# logicboard.net
KiCad netlist of a schematic drawn in EAGLE
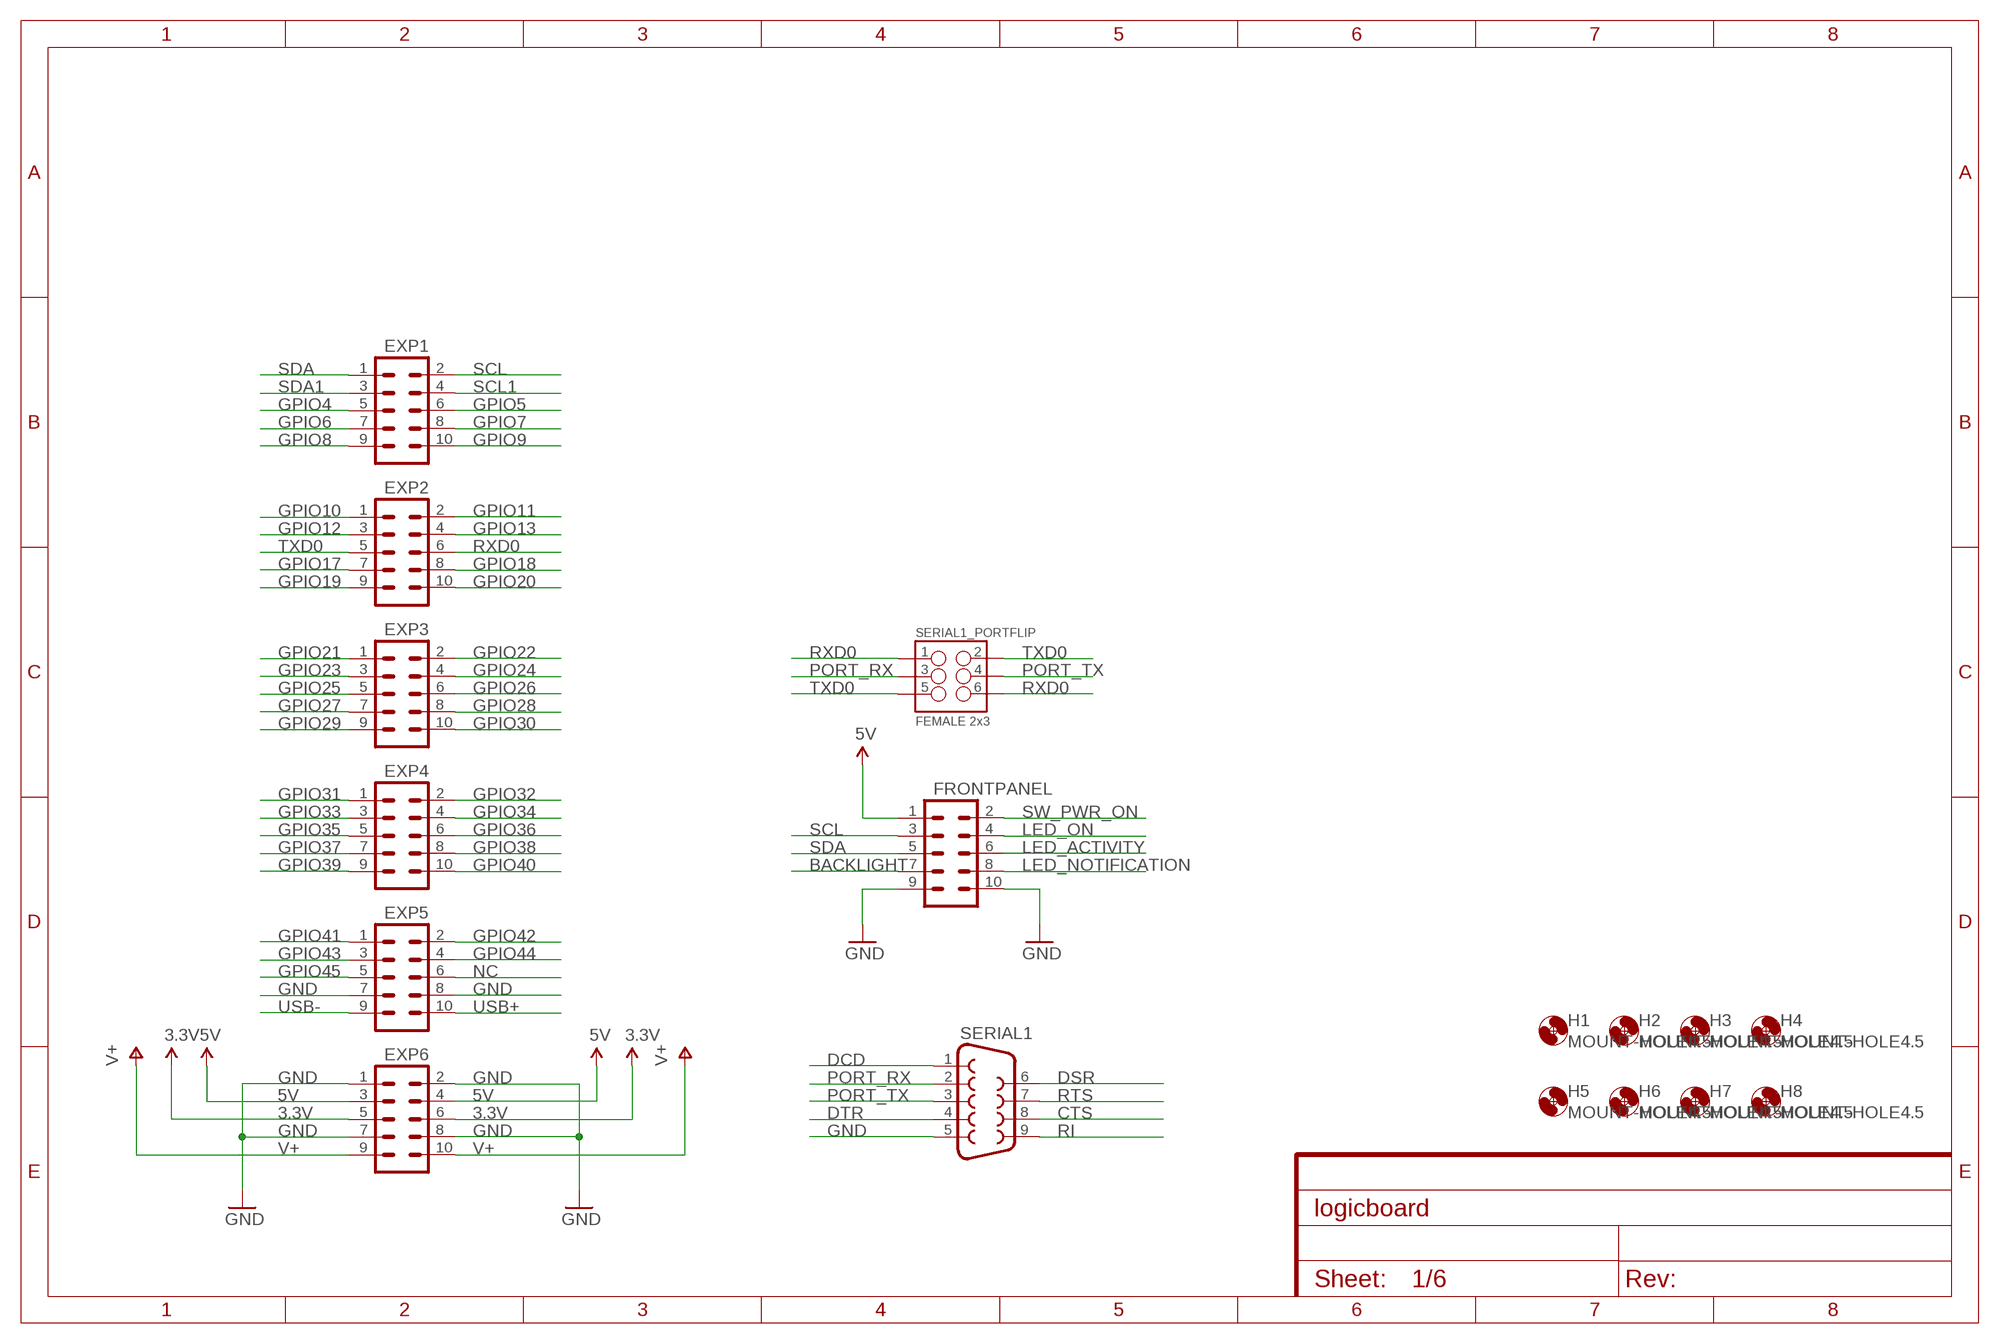
[diagram p0: schematic, sheet 1]
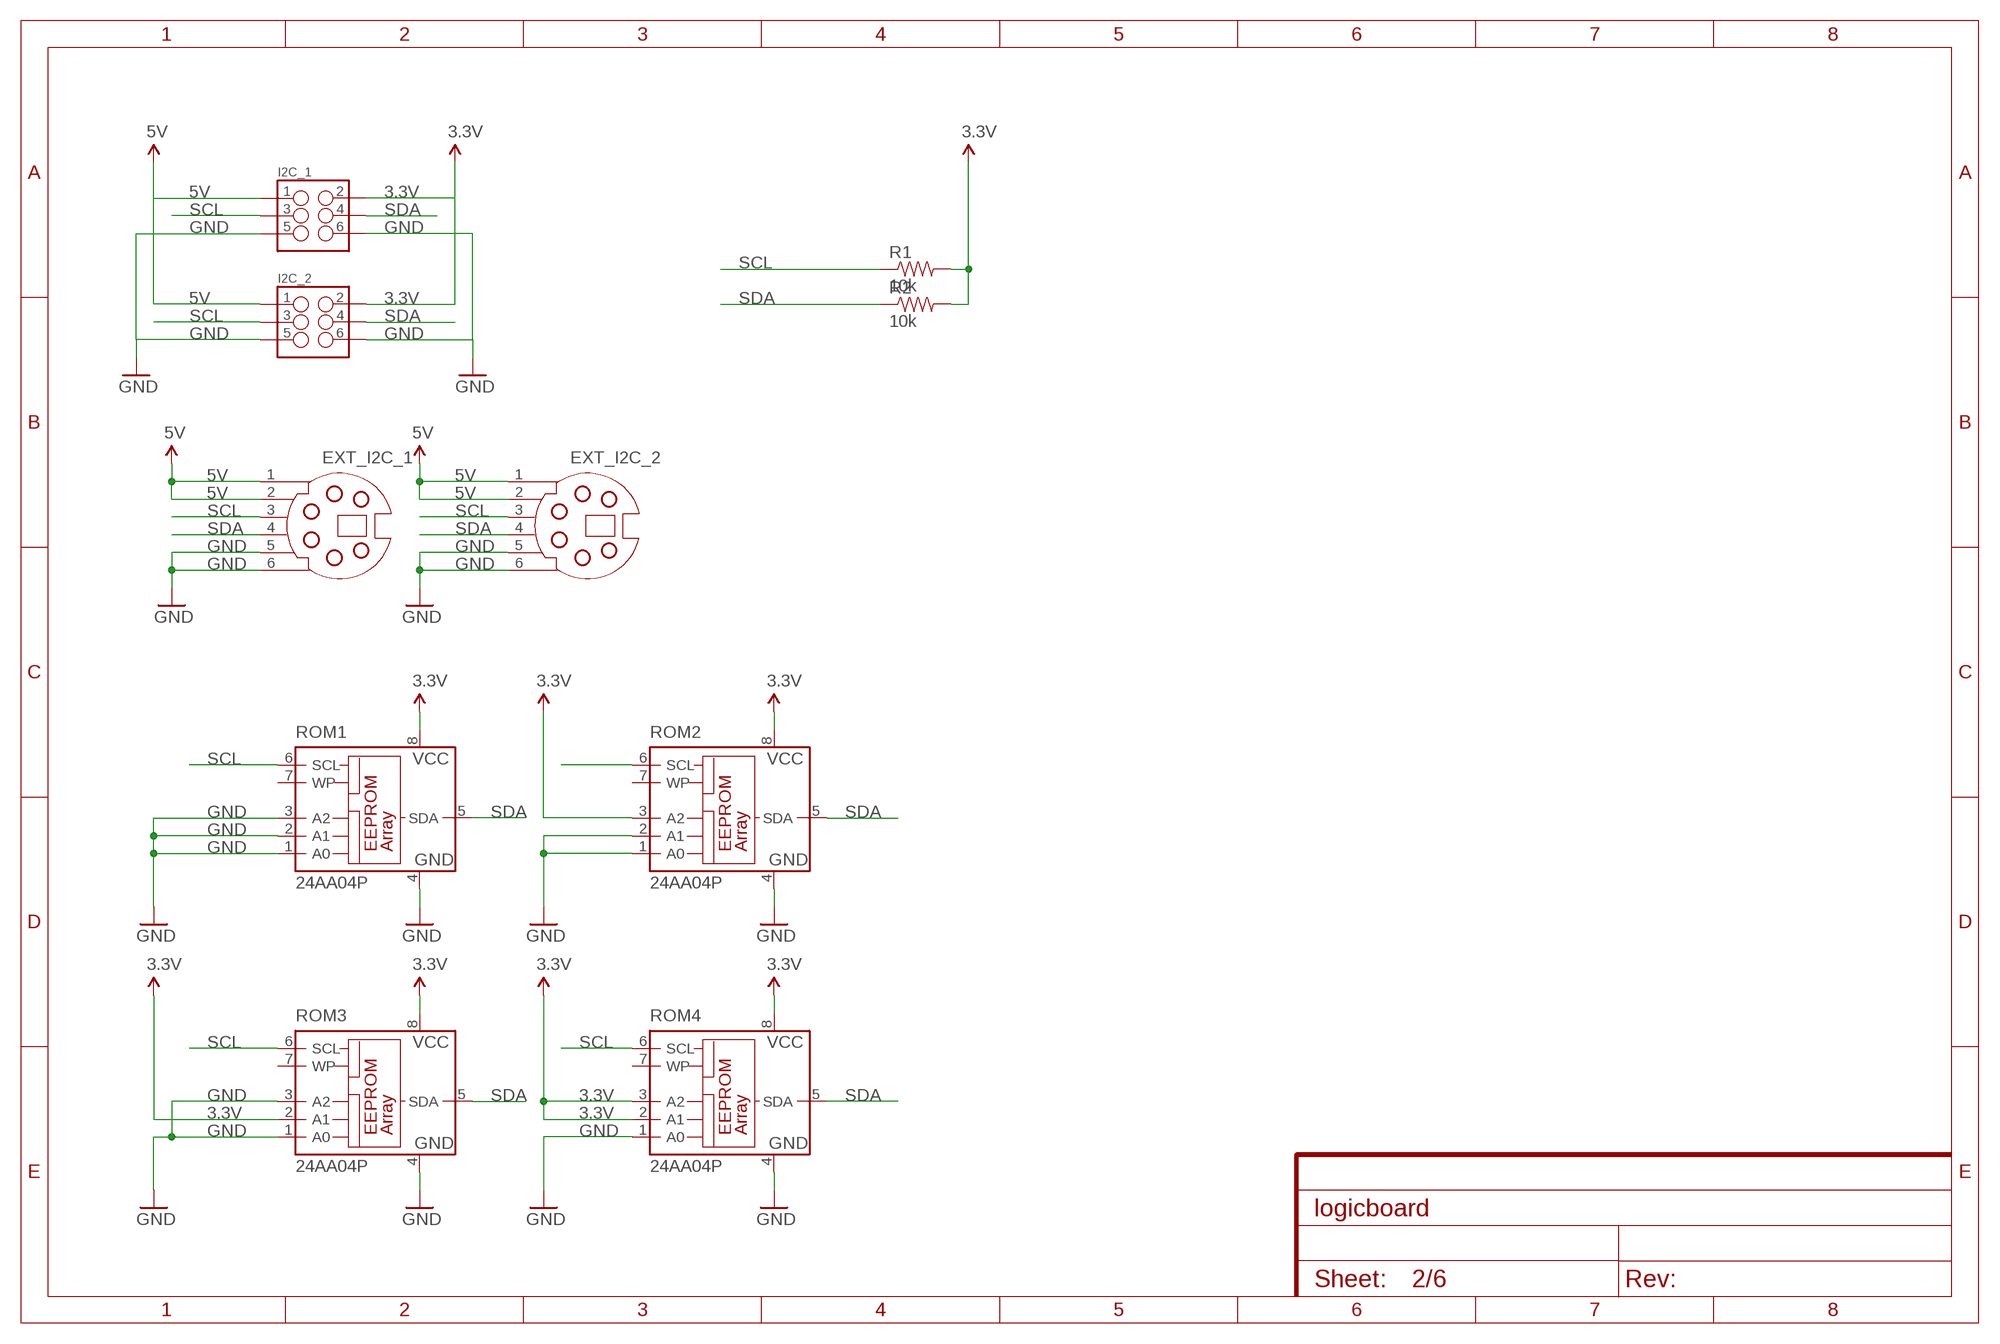
[diagram p1: schematic, sheet 2]
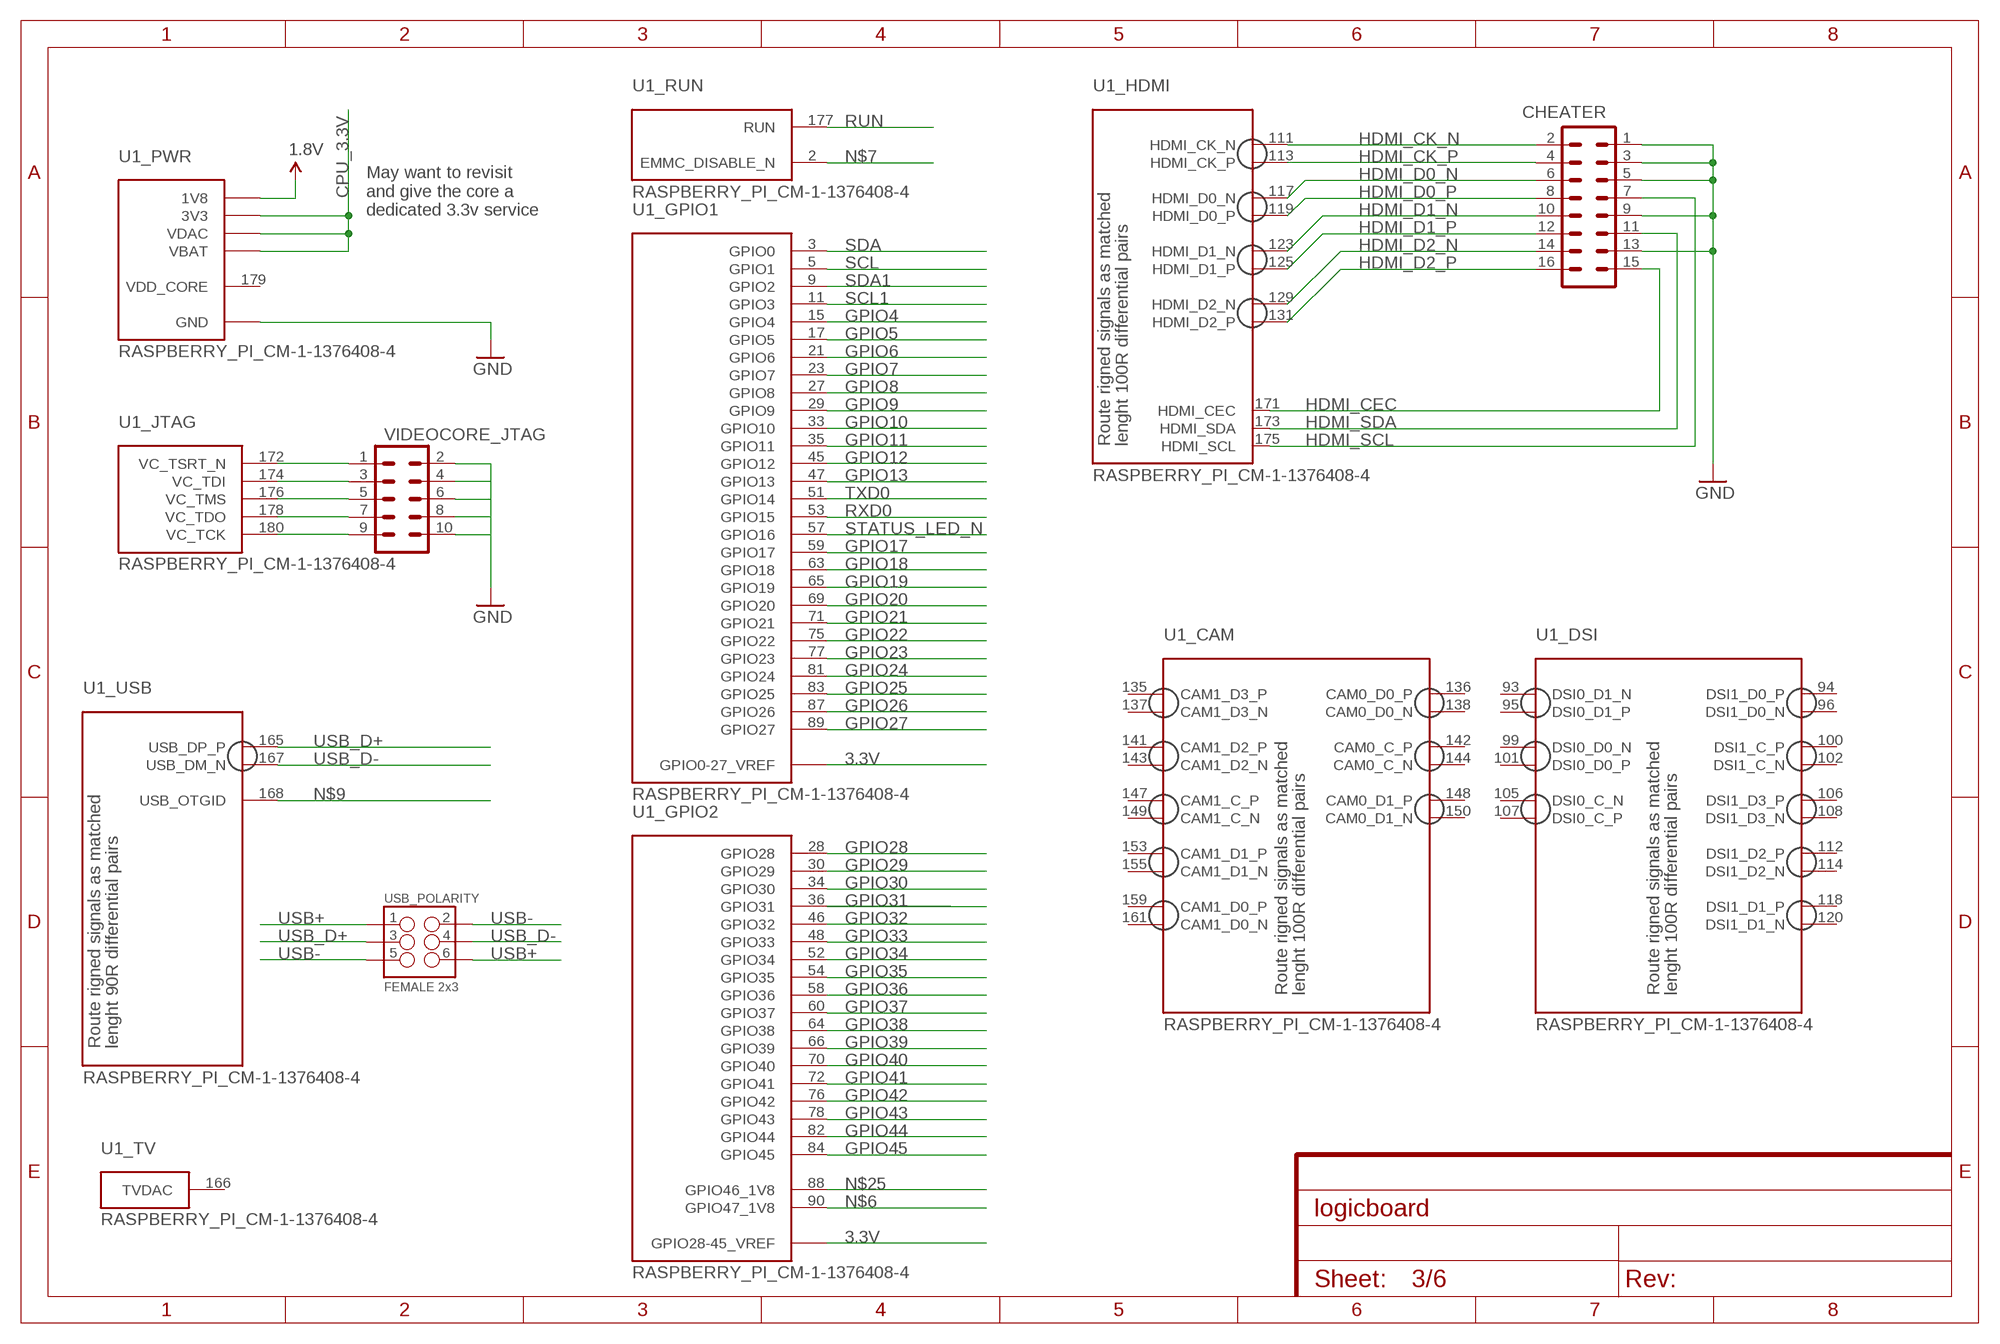
[diagram p2: schematic, sheet 3]
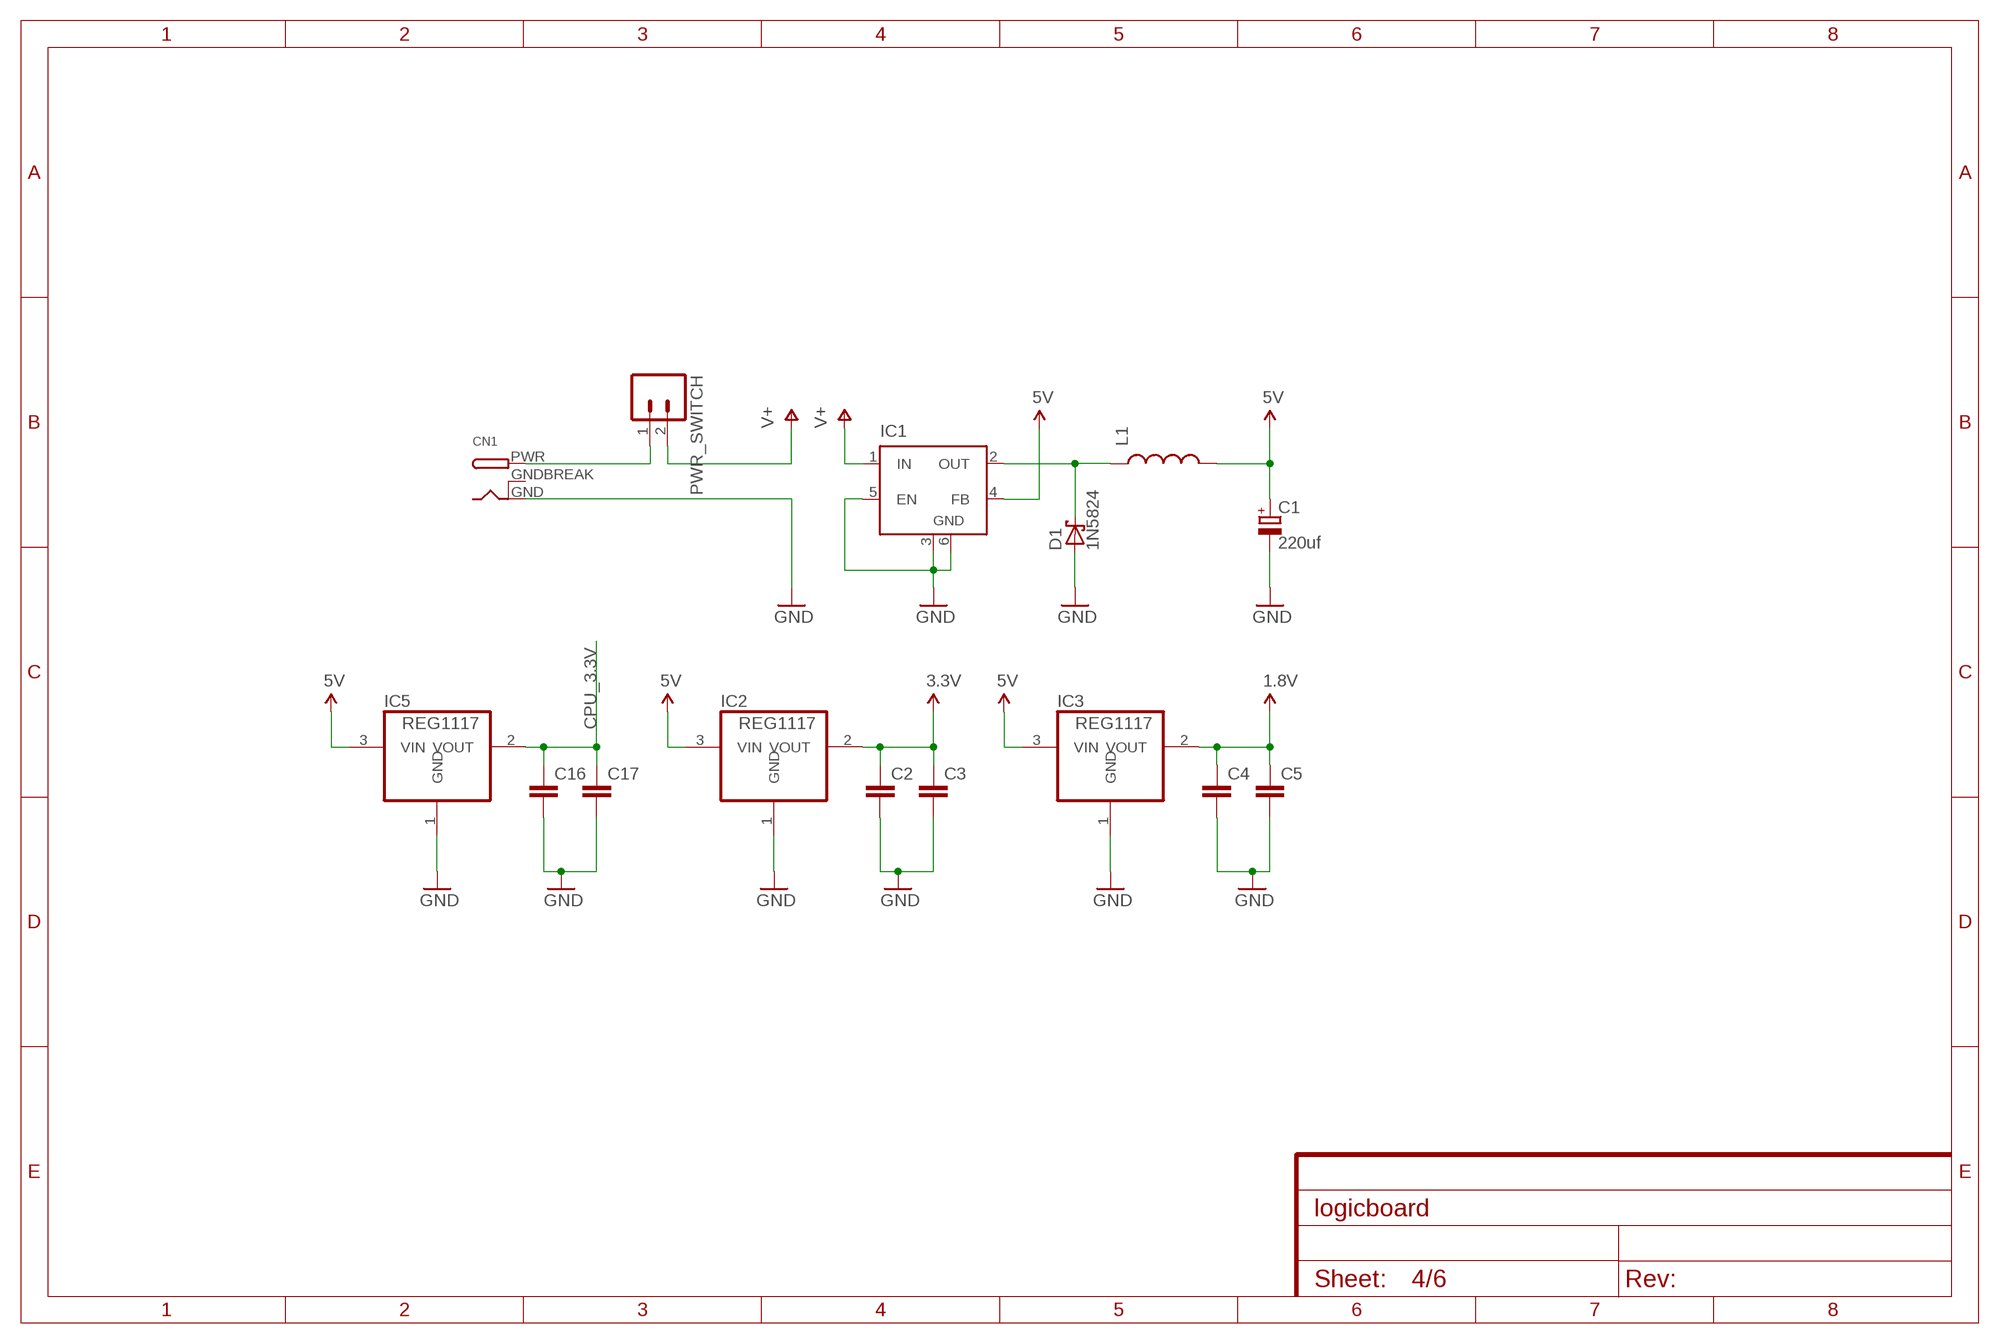
[diagram p3: schematic, sheet 4]
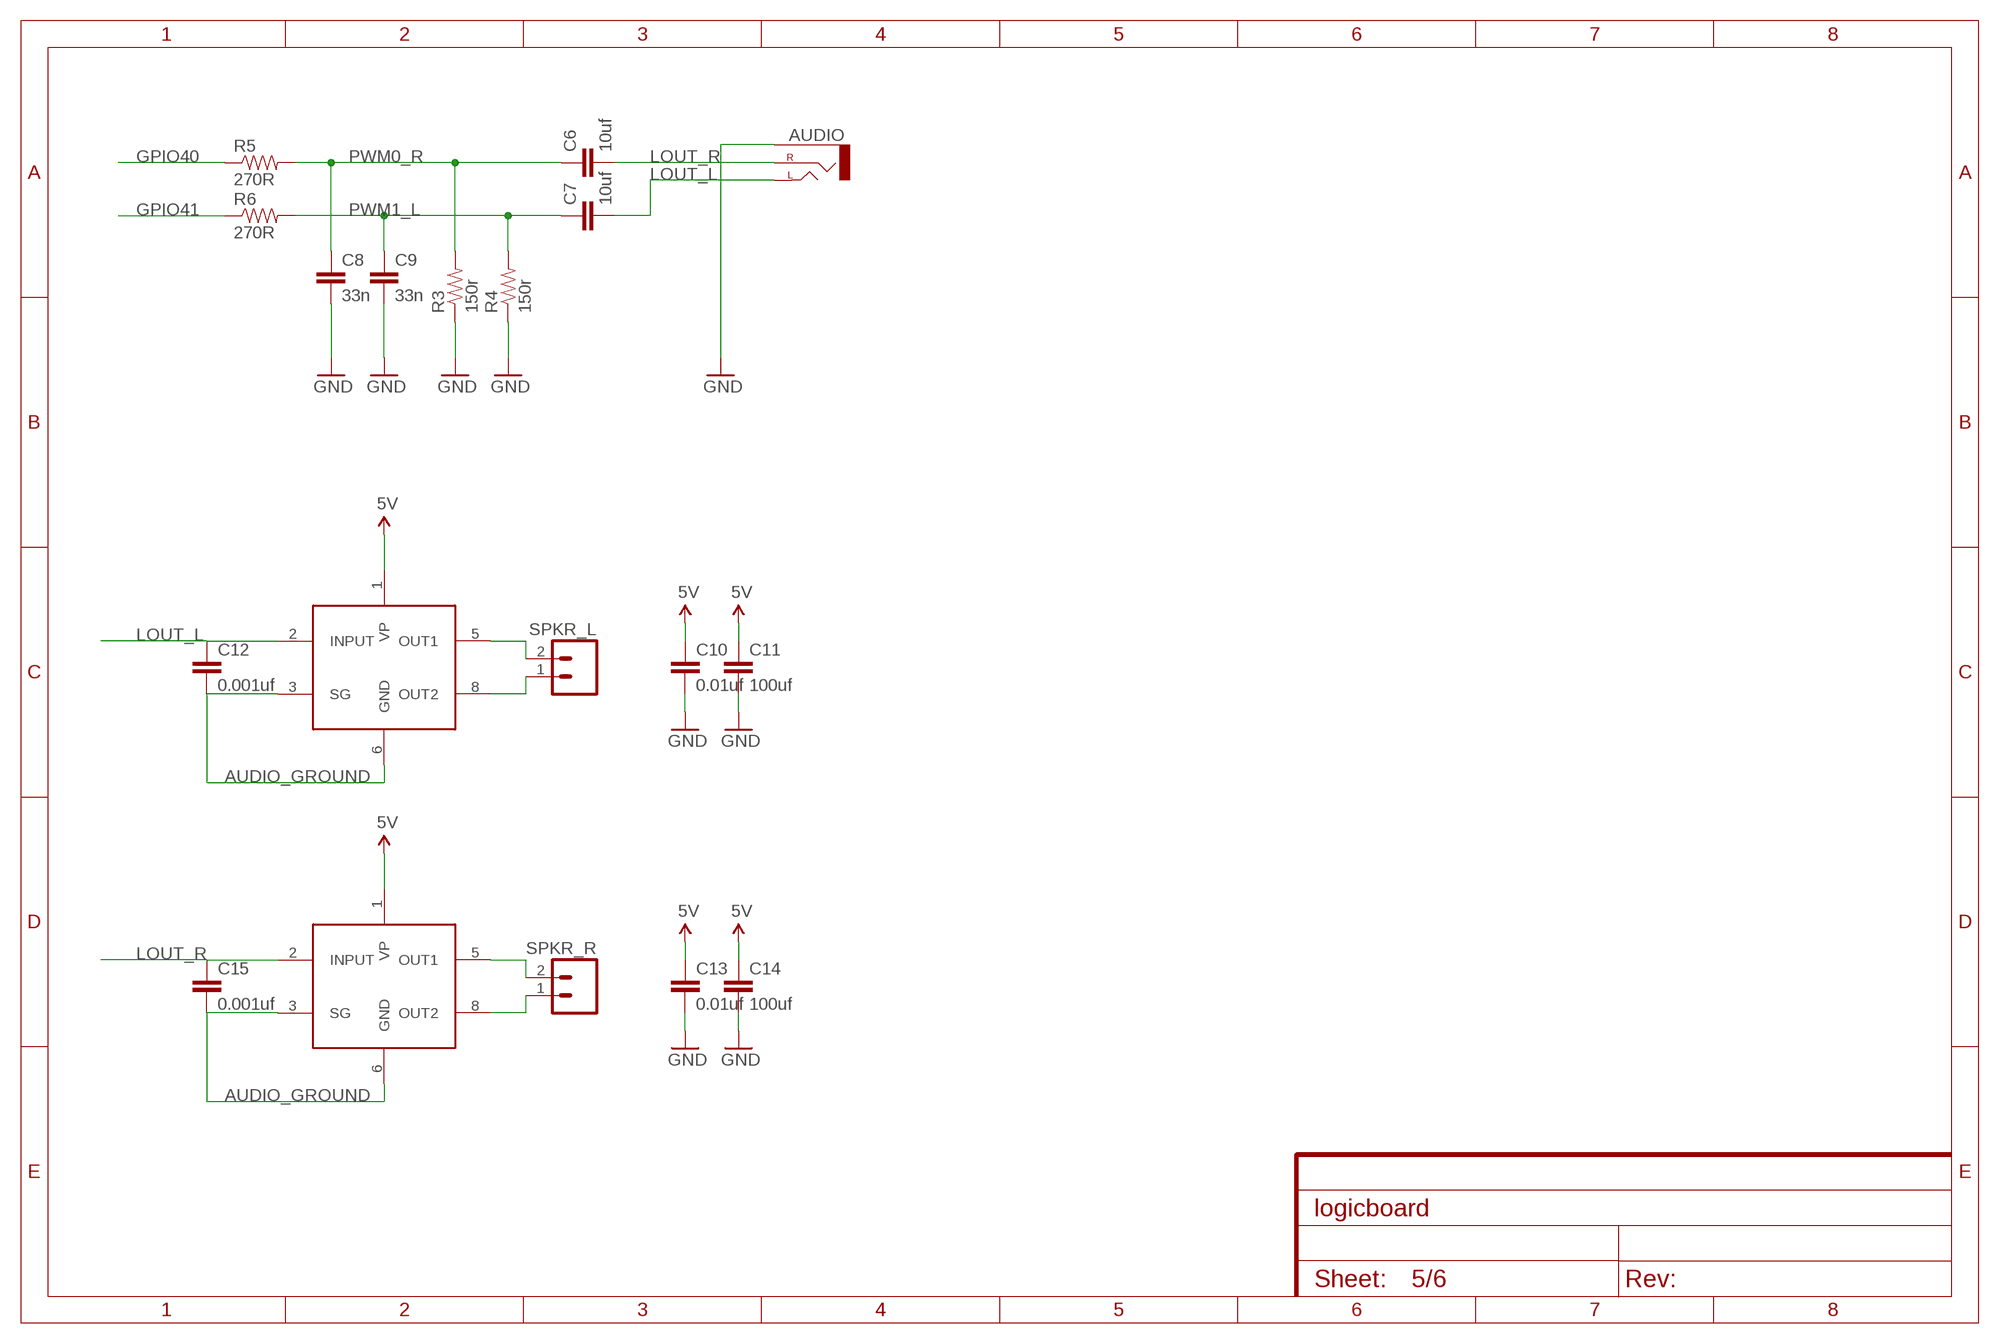
[diagram p4: schematic, sheet 5]
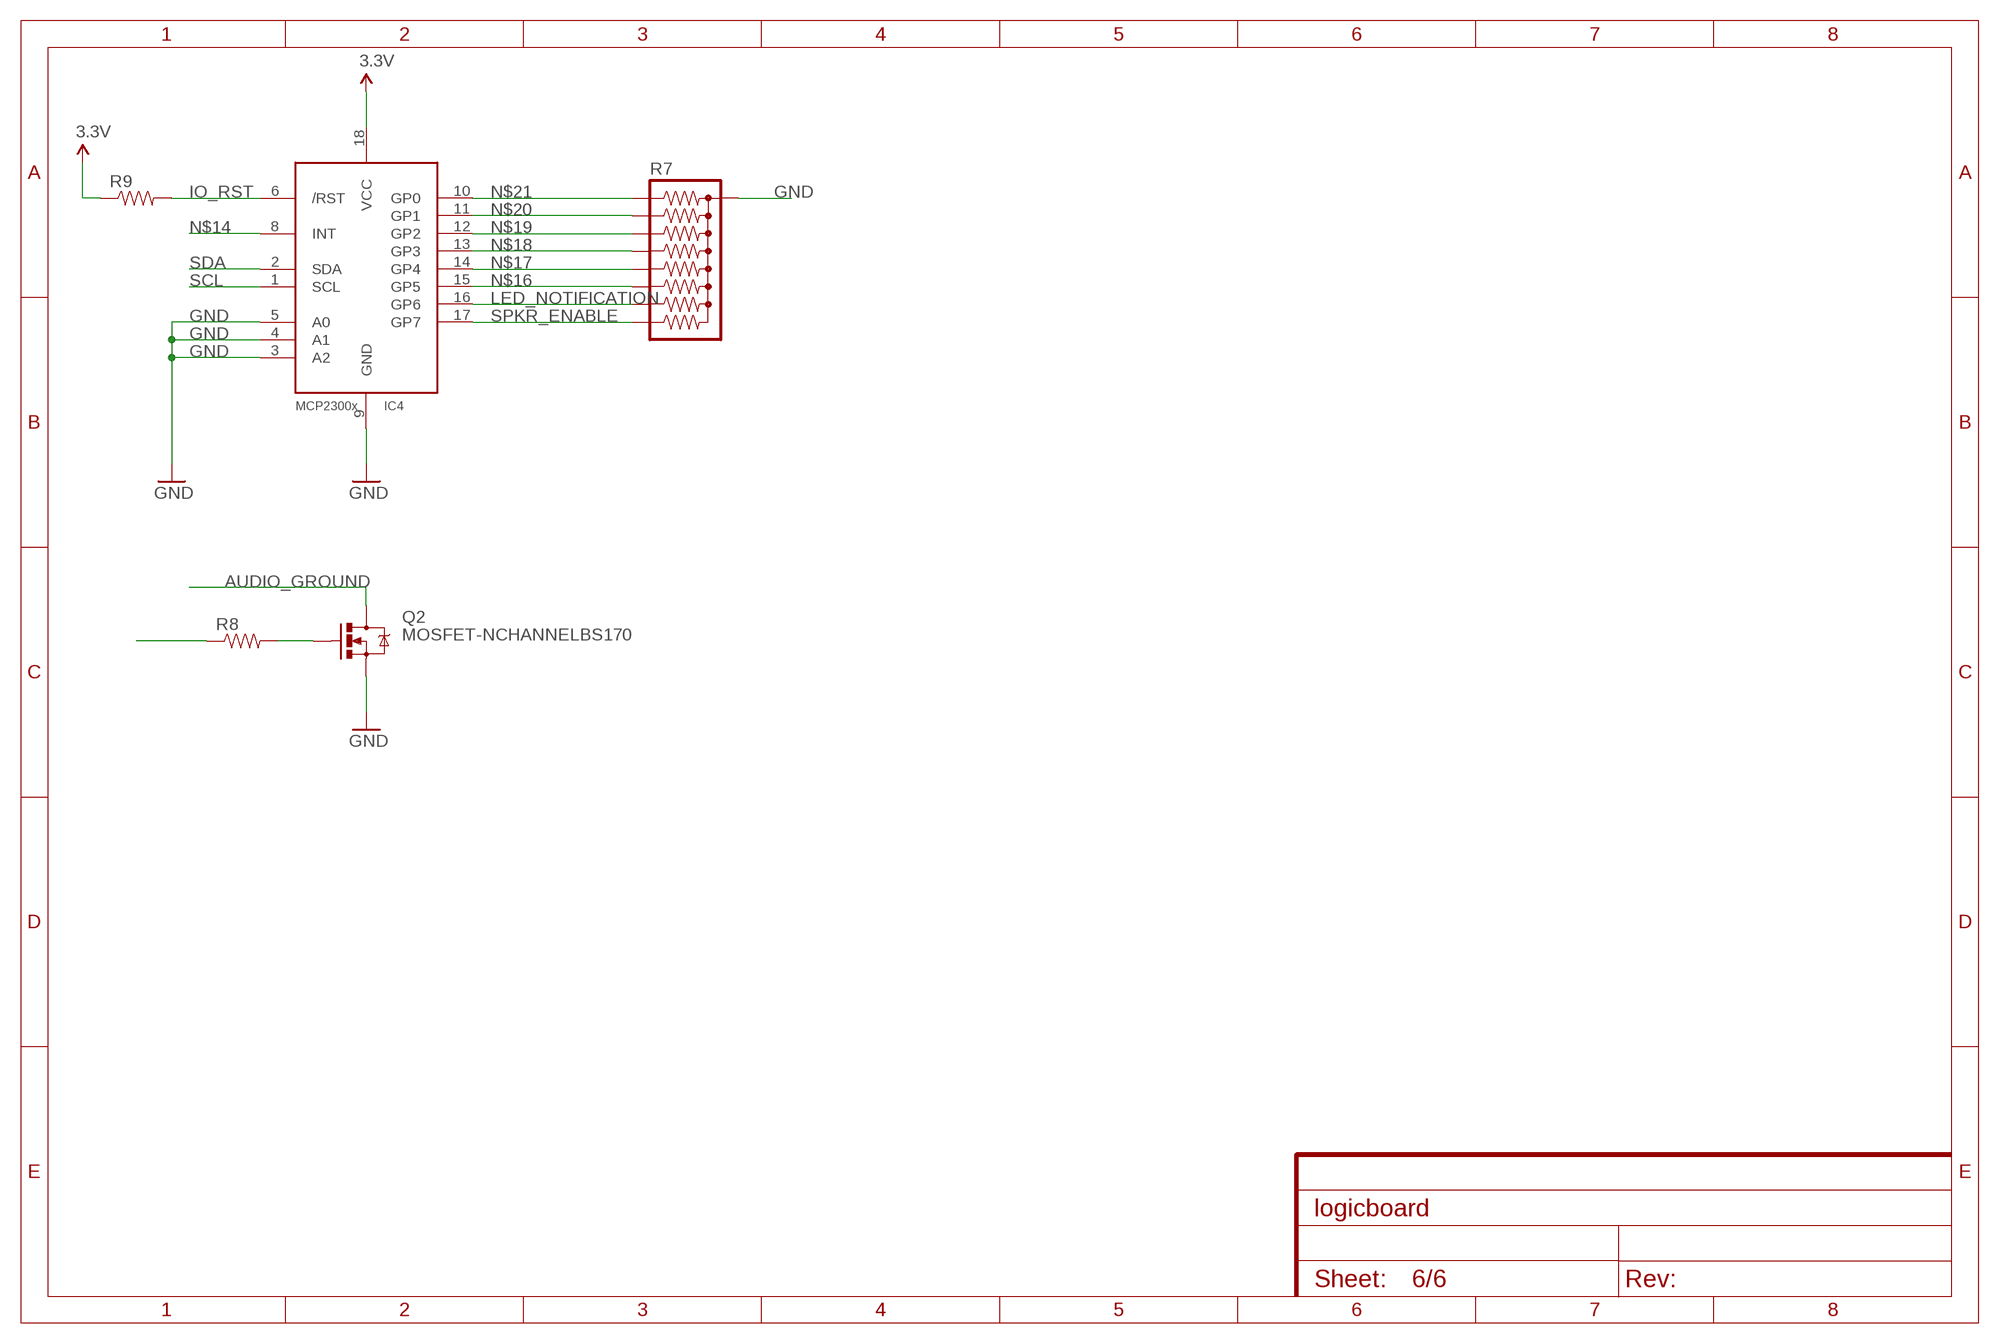
[diagram p5: schematic, sheet 6]

(export (version "E")
  (design (tool "Eeschema 10.0.6"))
  (components
    (comp (ref "AUDIO")
      (value "AUDIO-JACKPTH")
      (footprint "eagle-import:AUDIO-JACK")
      (libsource (lib "eagle-import") (part "AUDIO-JACKPTH"))
    )
    (comp (ref "C6")
      (value "10uf")
      (footprint "eagle-import:CAP-PTH-SMALLEZ")
      (libsource (lib "eagle-import") (part "CAPEZ"))
    )
    (comp (ref "C7")
      (value "10uf")
      (footprint "eagle-import:CAP-PTH-SMALLEZ")
      (libsource (lib "eagle-import") (part "CAPEZ"))
    )
    (comp (ref "C8")
      (value "33n")
      (footprint "eagle-import:CAP-PTH-SMALLEZ")
      (libsource (lib "eagle-import") (part "CAPEZ"))
    )
    (comp (ref "C9")
      (value "33n")
      (footprint "eagle-import:CAP-PTH-SMALLEZ")
      (libsource (lib "eagle-import") (part "CAPEZ"))
    )
    (comp (ref "C10")
      (value "0.01uf")
      (footprint "eagle-import:CAP-PTH-SMALLEZ")
      (libsource (lib "eagle-import") (part "CAPEZ"))
    )
    (comp (ref "C11")
      (value "100uf")
      (footprint "eagle-import:CAP-PTH-SMALLEZ")
      (libsource (lib "eagle-import") (part "CAPEZ"))
    )
    (comp (ref "C12")
      (value "0.001uf")
      (footprint "eagle-import:CAP-PTH-SMALLEZ")
      (libsource (lib "eagle-import") (part "CAPEZ"))
    )
    (comp (ref "C13")
      (value "0.01uf")
      (footprint "eagle-import:CAP-PTH-SMALLEZ")
      (libsource (lib "eagle-import") (part "CAPEZ"))
    )
    (comp (ref "C14")
      (value "100uf")
      (footprint "eagle-import:CAP-PTH-SMALLEZ")
      (libsource (lib "eagle-import") (part "CAPEZ"))
    )
    (comp (ref "C15")
      (value "0.001uf")
      (footprint "eagle-import:CAP-PTH-SMALLEZ")
      (libsource (lib "eagle-import") (part "CAPEZ"))
    )
    (comp (ref "R3")
      (value "150r")
      (footprint "eagle-import:AXIAL-0.3EZ")
      (libsource (lib "eagle-import") (part "RESISTOREZ"))
    )
    (comp (ref "R4")
      (value "150r")
      (footprint "eagle-import:AXIAL-0.3EZ")
      (libsource (lib "eagle-import") (part "RESISTOREZ"))
    )
    (comp (ref "R5")
      (value "270R")
      (footprint "eagle-import:AXIAL-0.3EZ")
      (libsource (lib "eagle-import") (part "RESISTOREZ"))
    )
    (comp (ref "R6")
      (value "270R")
      (footprint "eagle-import:AXIAL-0.3EZ")
      (libsource (lib "eagle-import") (part "RESISTOREZ"))
    )
    (comp (ref "SPKR_L")
      (value "M02JST-PTH-2-KIT")
      (footprint "eagle-import:JST-2-PTH-KIT")
      (libsource (lib "eagle-import") (part "M02JST-PTH-2-KIT"))
    )
    (comp (ref "SPKR_R")
      (value "M02JST-PTH-2-KIT")
      (footprint "eagle-import:JST-2-PTH-KIT")
      (libsource (lib "eagle-import") (part "M02JST-PTH-2-KIT"))
    )
    (comp (ref "U$1")
      (value "TDA7052")
      (footprint "eagle-import:DIL08")
      (libsource (lib "eagle-import") (part "TDA7052"))
    )
    (comp (ref "U$2")
      (value "TDA7052")
      (footprint "eagle-import:DIL08")
      (libsource (lib "eagle-import") (part "TDA7052"))
    )
    (comp (ref "EXP1")
      (value "M05X2SHD_LOCK")
      (footprint "eagle-import:2X5-SHROUDED_LOCK")
      (libsource (lib "eagle-import") (part "M05X2SHD_LOCK"))
    )
    (comp (ref "EXP2")
      (value "M05X2SHD_LOCK")
      (footprint "eagle-import:2X5-SHROUDED_LOCK")
      (libsource (lib "eagle-import") (part "M05X2SHD_LOCK"))
    )
    (comp (ref "EXP3")
      (value "M05X2SHD_LOCK")
      (footprint "eagle-import:2X5-SHROUDED_LOCK")
      (libsource (lib "eagle-import") (part "M05X2SHD_LOCK"))
    )
    (comp (ref "EXP4")
      (value "M05X2SHD_LOCK")
      (footprint "eagle-import:2X5-SHROUDED_LOCK")
      (libsource (lib "eagle-import") (part "M05X2SHD_LOCK"))
    )
    (comp (ref "EXP5")
      (value "M05X2SHD_LOCK")
      (footprint "eagle-import:2X5-SHROUDED_LOCK")
      (libsource (lib "eagle-import") (part "M05X2SHD_LOCK"))
    )
    (comp (ref "EXP6")
      (value "M05X2SHD_LOCK")
      (footprint "eagle-import:2X5-SHROUDED_LOCK")
      (libsource (lib "eagle-import") (part "M05X2SHD_LOCK"))
    )
    (comp (ref "FRONTPANEL")
      (value "M05X2SHD_LOCK")
      (footprint "eagle-import:2X5-SHROUDED_LOCK")
      (libsource (lib "eagle-import") (part "M05X2SHD_LOCK"))
    )
    (comp (ref "H1")
      (value "MOUNT-HOLE4.5")
      (footprint "eagle-import:4,5")
      (libsource (lib "eagle-import") (part "MOUNT-HOLE4.5"))
    )
    (comp (ref "H2")
      (value "MOUNT-HOLE4.5")
      (footprint "eagle-import:4,5")
      (libsource (lib "eagle-import") (part "MOUNT-HOLE4.5"))
    )
    (comp (ref "H3")
      (value "MOUNT-HOLE4.5")
      (footprint "eagle-import:4,5")
      (libsource (lib "eagle-import") (part "MOUNT-HOLE4.5"))
    )
    (comp (ref "H4")
      (value "MOUNT-HOLE4.5")
      (footprint "eagle-import:4,5")
      (libsource (lib "eagle-import") (part "MOUNT-HOLE4.5"))
    )
    (comp (ref "H5")
      (value "MOUNT-HOLE4.5")
      (footprint "eagle-import:4,5")
      (libsource (lib "eagle-import") (part "MOUNT-HOLE4.5"))
    )
    (comp (ref "H6")
      (value "MOUNT-HOLE4.5")
      (footprint "eagle-import:4,5")
      (libsource (lib "eagle-import") (part "MOUNT-HOLE4.5"))
    )
    (comp (ref "H7")
      (value "MOUNT-HOLE4.5")
      (footprint "eagle-import:4,5")
      (libsource (lib "eagle-import") (part "MOUNT-HOLE4.5"))
    )
    (comp (ref "H8")
      (value "MOUNT-HOLE4.5")
      (footprint "eagle-import:4,5")
      (libsource (lib "eagle-import") (part "MOUNT-HOLE4.5"))
    )
    (comp (ref "SERIAL1")
      (value "F09HP")
      (footprint "eagle-import:F09HP")
      (libsource (lib "eagle-import") (part "F09HP"))
    )
    (comp (ref "SERIAL1_PORTFLIP")
      (value "FEMALE 2x3")
      (footprint "eagle-import:2X3")
      (libsource (lib "eagle-import") (part "M03X2FEMALE"))
    )
    (comp (ref "C1")
      (value "220uf")
      (footprint "eagle-import:E2,5-6")
      (libsource (lib "eagle-import") (part "CPOL-EUE2.5-6"))
    )
    (comp (ref "C2")
      (value "CAP1206")
      (footprint "eagle-import:1206")
      (libsource (lib "eagle-import") (part "CAP1206"))
    )
    (comp (ref "C3")
      (value "CAP1206")
      (footprint "eagle-import:1206")
      (libsource (lib "eagle-import") (part "CAP1206"))
    )
    (comp (ref "C4")
      (value "CAP1206")
      (footprint "eagle-import:1206")
      (libsource (lib "eagle-import") (part "CAP1206"))
    )
    (comp (ref "C5")
      (value "CAP1206")
      (footprint "eagle-import:1206")
      (libsource (lib "eagle-import") (part "CAP1206"))
    )
    (comp (ref "C16")
      (value "CAP1206")
      (footprint "eagle-import:1206")
      (libsource (lib "eagle-import") (part "CAP1206"))
    )
    (comp (ref "C17")
      (value "CAP1206")
      (footprint "eagle-import:1206")
      (libsource (lib "eagle-import") (part "CAP1206"))
    )
    (comp (ref "CN1")
      (value "DCBARRELPTH")
      (footprint "eagle-import:DCJACK_2MM_PTH")
      (libsource (lib "eagle-import") (part "DCBARRELPTH"))
    )
    (comp (ref "D1")
      (value "1N5824")
      (footprint "eagle-import:DO41-7.6")
      (libsource (lib "eagle-import") (part "1N5817-B"))
    )
    (comp (ref "IC1")
      (value "LM2596S")
      (footprint "eagle-import:TO263-5")
      (libsource (lib "eagle-import") (part "LM2596S"))
    )
    (comp (ref "IC2")
      (value "REG1117")
      (footprint "eagle-import:SOT223")
      (libsource (lib "eagle-import") (part "REG1117"))
    )
    (comp (ref "IC3")
      (value "REG1117")
      (footprint "eagle-import:SOT223")
      (libsource (lib "eagle-import") (part "REG1117"))
    )
    (comp (ref "IC5")
      (value "REG1117")
      (footprint "eagle-import:SOT223")
      (libsource (lib "eagle-import") (part "REG1117"))
    )
    (comp (ref "L1")
      (value "INDUCTORSRU1038")
      (footprint "eagle-import:SRU1038")
      (libsource (lib "eagle-import") (part "INDUCTORSRU1038"))
    )
    (comp (ref "PWR_SWITCH")
      (value "M02POLAR")
      (footprint "eagle-import:MOLEX-1X2")
      (libsource (lib "eagle-import") (part "M02POLAR"))
    )
    (comp (ref "CHEATER")
      (value "M08X2")
      (footprint "eagle-import:2X8")
      (libsource (lib "eagle-import") (part "M08X2"))
    )
    (comp (ref "U1")
      (value "RASPBERRY_PI_CM-1-1376408-4")
      (footprint "eagle-import:1-1376408-4")
      (libsource (lib "eagle-import") (part "RASPBERRY_PI_CM-1-1376408-4"))
    )
    (comp (ref "USB_POLARITY")
      (value "FEMALE 2x3")
      (footprint "eagle-import:2X3")
      (libsource (lib "eagle-import") (part "M03X2FEMALE"))
    )
    (comp (ref "VIDEOCORE_JTAG")
      (value "M05X2SHD_LOCK")
      (footprint "eagle-import:2X5-SHROUDED_LOCK")
      (libsource (lib "eagle-import") (part "M05X2SHD_LOCK"))
    )
    (comp (ref "EXT_I2C_1")
      (value "MDSSV-BC06")
      (footprint "eagle-import:SSV-BC06")
      (libsource (lib "eagle-import") (part "MDSSV-BC06"))
    )
    (comp (ref "EXT_I2C_2")
      (value "MDSSV-BC06")
      (footprint "eagle-import:SSV-BC06")
      (libsource (lib "eagle-import") (part "MDSSV-BC06"))
    )
    (comp (ref "I2C_1")
      (value "M03X2SHROUD")
      (footprint "eagle-import:2X3-SHROUDED")
      (libsource (lib "eagle-import") (part "M03X2SHROUD"))
    )
    (comp (ref "I2C_2")
      (value "M03X2SHROUD")
      (footprint "eagle-import:2X3-SHROUDED")
      (libsource (lib "eagle-import") (part "M03X2SHROUD"))
    )
    (comp (ref "R1")
      (value "10k")
      (footprint "eagle-import:AXIAL-0.3EZ")
      (libsource (lib "eagle-import") (part "10KOHM-1/4W-1%(PTH)HORIZ-KIT"))
    )
    (comp (ref "R2")
      (value "10k")
      (footprint "eagle-import:AXIAL-0.3EZ")
      (libsource (lib "eagle-import") (part "10KOHM-1/4W-1%(PTH)HORIZ-KIT"))
    )
    (comp (ref "ROM1")
      (value "24AA04P")
      (footprint "eagle-import:DIL8")
      (fields (field (name "MPN") "24AA04-I/P"))
      (libsource (lib "eagle-import") (part "24PAA04"))
    )
    (comp (ref "ROM2")
      (value "24AA04P")
      (footprint "eagle-import:DIL8")
      (fields (field (name "MPN") "24AA04-I/P"))
      (libsource (lib "eagle-import") (part "24PAA04"))
    )
    (comp (ref "ROM3")
      (value "24AA04P")
      (footprint "eagle-import:DIL8")
      (fields (field (name "MPN") "24AA04-I/P"))
      (libsource (lib "eagle-import") (part "24PAA04"))
    )
    (comp (ref "ROM4")
      (value "24AA04P")
      (footprint "eagle-import:DIL8")
      (fields (field (name "MPN") "24AA04-I/P"))
      (libsource (lib "eagle-import") (part "24PAA04"))
    )
    (comp (ref "IC4")
      (value "MCP2300X/P")
      (footprint "eagle-import:DIL18")
      (libsource (lib "eagle-import") (part "MCP2300X/P"))
    )
    (comp (ref "Q2")
      (value "MOSFET-NCHANNELBS170")
      (footprint "eagle-import:TO-92")
      (libsource (lib "eagle-import") (part "MOSFET-NCHANNELBS170"))
    )
    (comp (ref "R7")
      (value "RPACK-BUSSED-8-SIP-PTH-8")
      (footprint "eagle-import:RPACK-SIP-PTH-8")
      (libsource (lib "eagle-import") (part "RPACK-BUSSED-8-SIP-PTH-8"))
    )
    (comp (ref "R8")
      (value "RESISTOREZ")
      (footprint "eagle-import:AXIAL-0.3EZ")
      (libsource (lib "eagle-import") (part "RESISTOREZ"))
    )
    (comp (ref "R9")
      (value "RESISTOREZ")
      (footprint "eagle-import:AXIAL-0.3EZ")
      (libsource (lib "eagle-import") (part "RESISTOREZ"))
    )
  )
  (nets
    (net (code "1") (name "1.8V") (class "Default")
      (node (ref "C4") (pin "1") (pinfunction "1_1") (pintype "passive"))
      (node (ref "C5") (pin "1") (pinfunction "1_1") (pintype "passive"))
      (node (ref "IC3") (pin "2") (pinfunction "VOUT_2") (pintype "output"))
      (node (ref "U1") (pin "183") (pinfunction "1V8_183") (pintype "bidirectional"))
      (node (ref "U1") (pin "184") (pinfunction "1V8_184") (pintype "bidirectional"))
      (node (ref "U1") (pin "185") (pinfunction "1V8_185") (pintype "bidirectional"))
      (node (ref "U1") (pin "186") (pinfunction "1V8_186") (pintype "bidirectional"))
    )
    (net (code "2") (name "3.3V") (class "Default")
      (node (ref "C2") (pin "1") (pinfunction "1_1") (pintype "passive"))
      (node (ref "C3") (pin "1") (pinfunction "1_1") (pintype "passive"))
      (node (ref "EXP6") (pin "5") (pinfunction "5_5") (pintype "passive"))
      (node (ref "EXP6") (pin "6") (pinfunction "6_6") (pintype "passive"))
      (node (ref "I2C_1") (pin "2") (pinfunction "2_2") (pintype "bidirectional"))
      (node (ref "I2C_2") (pin "2") (pinfunction "2_2") (pintype "bidirectional"))
      (node (ref "IC2") (pin "2") (pinfunction "VOUT_2") (pintype "output"))
      (node (ref "IC4") (pin "18") (pinfunction "VCC_18") (pintype "power_in"))
      (node (ref "R1") (pin "P$2") (pinfunction "2_P$2") (pintype "passive"))
      (node (ref "R2") (pin "P$2") (pinfunction "2_P$2") (pintype "passive"))
      (node (ref "R9") (pin "P$1") (pinfunction "1_P$1") (pintype "passive"))
      (node (ref "ROM1") (pin "8") (pinfunction "VCC_8") (pintype "power_in"))
      (node (ref "ROM2") (pin "3") (pinfunction "A2_3") (pintype "input"))
      (node (ref "ROM2") (pin "8") (pinfunction "VCC_8") (pintype "power_in"))
      (node (ref "ROM3") (pin "2") (pinfunction "A1_2") (pintype "input"))
      (node (ref "ROM3") (pin "8") (pinfunction "VCC_8") (pintype "power_in"))
      (node (ref "ROM4") (pin "2") (pinfunction "A1_2") (pintype "input"))
      (node (ref "ROM4") (pin "3") (pinfunction "A2_3") (pintype "input"))
      (node (ref "ROM4") (pin "8") (pinfunction "VCC_8") (pintype "power_in"))
      (node (ref "U1") (pin "39") (pinfunction "GPIO0-27_VREF_39") (pintype "bidirectional"))
      (node (ref "U1") (pin "40") (pinfunction "GPIO0-27_VREF_40") (pintype "bidirectional"))
      (node (ref "U1") (pin "41") (pinfunction "GPIO28-45_VREF_41") (pintype "bidirectional"))
      (node (ref "U1") (pin "42") (pinfunction "GPIO28-45_VREF_42") (pintype "bidirectional"))
    )
    (net (code "3") (name "5V") (class "Default")
      (node (ref "C1") (pin "+") (pinfunction "+_+") (pintype "passive"))
      (node (ref "C10") (pin "1") (pinfunction "1_1") (pintype "passive"))
      (node (ref "C11") (pin "1") (pinfunction "1_1") (pintype "passive"))
      (node (ref "C13") (pin "1") (pinfunction "1_1") (pintype "passive"))
      (node (ref "C14") (pin "1") (pinfunction "1_1") (pintype "passive"))
      (node (ref "EXP6") (pin "3") (pinfunction "3_3") (pintype "passive"))
      (node (ref "EXP6") (pin "4") (pinfunction "4_4") (pintype "passive"))
      (node (ref "EXT_I2C_1") (pin "1") (pinfunction "1_1") (pintype "passive"))
      (node (ref "EXT_I2C_1") (pin "2") (pinfunction "2_2") (pintype "passive"))
      (node (ref "EXT_I2C_2") (pin "1") (pinfunction "1_1") (pintype "passive"))
      (node (ref "EXT_I2C_2") (pin "2") (pinfunction "2_2") (pintype "passive"))
      (node (ref "FRONTPANEL") (pin "1") (pinfunction "1_1") (pintype "passive"))
      (node (ref "I2C_1") (pin "1") (pinfunction "1_1") (pintype "bidirectional"))
      (node (ref "I2C_2") (pin "1") (pinfunction "1_1") (pintype "bidirectional"))
      (node (ref "IC1") (pin "4") (pinfunction "FB_4") (pintype "input"))
      (node (ref "IC2") (pin "3") (pinfunction "VIN_3") (pintype "input"))
      (node (ref "IC3") (pin "3") (pinfunction "VIN_3") (pintype "input"))
      (node (ref "IC5") (pin "3") (pinfunction "VIN_3") (pintype "input"))
      (node (ref "L1") (pin "2") (pinfunction "2_2") (pintype "passive"))
      (node (ref "U$1") (pin "1") (pinfunction "VP_1") (pintype "power_in"))
      (node (ref "U$2") (pin "1") (pinfunction "VP_1") (pintype "power_in"))
    )
    (net (code "4") (name "AUDIO_GROUND") (class "Default")
      (node (ref "C12") (pin "2") (pinfunction "2_2") (pintype "passive"))
      (node (ref "C15") (pin "2") (pinfunction "2_2") (pintype "passive"))
      (node (ref "Q2") (pin "1") (pinfunction "D_1") (pintype "passive"))
      (node (ref "U$1") (pin "3") (pinfunction "SG_3") (pintype "power_in"))
      (node (ref "U$1") (pin "6") (pinfunction "GND_6") (pintype "power_in"))
      (node (ref "U$2") (pin "3") (pinfunction "SG_3") (pintype "power_in"))
      (node (ref "U$2") (pin "6") (pinfunction "GND_6") (pintype "power_in"))
    )
    (net (code "5") (name "BACKLIGHT") (class "Default")
      (node (ref "FRONTPANEL") (pin "7") (pinfunction "7_7") (pintype "passive"))
    )
    (net (code "6") (name "CPU_3.3V") (class "Default")
      (node (ref "C16") (pin "1") (pinfunction "1_1") (pintype "passive"))
      (node (ref "C17") (pin "1") (pinfunction "1_1") (pintype "passive"))
      (node (ref "IC5") (pin "2") (pinfunction "VOUT_2") (pintype "output"))
      (node (ref "U1") (pin "189") (pinfunction "VDAC_189") (pintype "bidirectional"))
      (node (ref "U1") (pin "190") (pinfunction "VDAC_190") (pintype "bidirectional"))
      (node (ref "U1") (pin "191") (pinfunction "3V3_191") (pintype "bidirectional"))
      (node (ref "U1") (pin "192") (pinfunction "3V3_192") (pintype "bidirectional"))
      (node (ref "U1") (pin "193") (pinfunction "3V3_193") (pintype "bidirectional"))
      (node (ref "U1") (pin "194") (pinfunction "3V3_194") (pintype "bidirectional"))
      (node (ref "U1") (pin "197") (pinfunction "VBAT_197") (pintype "bidirectional"))
      (node (ref "U1") (pin "198") (pinfunction "VBAT_198") (pintype "bidirectional"))
      (node (ref "U1") (pin "199") (pinfunction "VBAT_199") (pintype "bidirectional"))
      (node (ref "U1") (pin "200") (pinfunction "VBAT_200") (pintype "bidirectional"))
    )
    (net (code "7") (name "CTS") (class "Default")
      (node (ref "SERIAL1") (pin "8") (pinfunction "8_8") (pintype "passive"))
    )
    (net (code "8") (name "DCD") (class "Default")
      (node (ref "SERIAL1") (pin "1") (pinfunction "1_1") (pintype "passive"))
    )
    (net (code "9") (name "DSR") (class "Default")
      (node (ref "SERIAL1") (pin "6") (pinfunction "6_6") (pintype "passive"))
    )
    (net (code "10") (name "DTR") (class "Default")
      (node (ref "SERIAL1") (pin "4") (pinfunction "4_4") (pintype "passive"))
    )
    (net (code "11") (name "GND") (class "Default")
      (node (ref "AUDIO") (pin "SLEEVE") (pinfunction "SLEEVE_SLEEVE") (pintype "bidirectional"))
      (node (ref "C1") (pin "-") (pinfunction "-_-") (pintype "passive"))
      (node (ref "C10") (pin "2") (pinfunction "2_2") (pintype "passive"))
      (node (ref "C11") (pin "2") (pinfunction "2_2") (pintype "passive"))
      (node (ref "C13") (pin "2") (pinfunction "2_2") (pintype "passive"))
      (node (ref "C14") (pin "2") (pinfunction "2_2") (pintype "passive"))
      (node (ref "C16") (pin "2") (pinfunction "2_2") (pintype "passive"))
      (node (ref "C17") (pin "2") (pinfunction "2_2") (pintype "passive"))
      (node (ref "C2") (pin "2") (pinfunction "2_2") (pintype "passive"))
      (node (ref "C3") (pin "2") (pinfunction "2_2") (pintype "passive"))
      (node (ref "C4") (pin "2") (pinfunction "2_2") (pintype "passive"))
      (node (ref "C5") (pin "2") (pinfunction "2_2") (pintype "passive"))
      (node (ref "C8") (pin "2") (pinfunction "2_2") (pintype "passive"))
      (node (ref "C9") (pin "2") (pinfunction "2_2") (pintype "passive"))
      (node (ref "CHEATER") (pin "1") (pinfunction "1_1") (pintype "passive"))
      (node (ref "CHEATER") (pin "13") (pinfunction "13_13") (pintype "passive"))
      (node (ref "CHEATER") (pin "3") (pinfunction "3_3") (pintype "passive"))
      (node (ref "CHEATER") (pin "5") (pinfunction "5_5") (pintype "passive"))
      (node (ref "CHEATER") (pin "9") (pinfunction "9_9") (pintype "passive"))
      (node (ref "CN1") (pin "GND") (pinfunction "GND_GND") (pintype "power_in"))
      (node (ref "D1") (pin "A") (pinfunction "A_A") (pintype "passive"))
      (node (ref "EXP5") (pin "7") (pinfunction "7_7") (pintype "passive"))
      (node (ref "EXP5") (pin "8") (pinfunction "8_8") (pintype "passive"))
      (node (ref "EXP6") (pin "1") (pinfunction "1_1") (pintype "passive"))
      (node (ref "EXP6") (pin "2") (pinfunction "2_2") (pintype "passive"))
      (node (ref "EXP6") (pin "7") (pinfunction "7_7") (pintype "passive"))
      (node (ref "EXP6") (pin "8") (pinfunction "8_8") (pintype "passive"))
      (node (ref "EXT_I2C_1") (pin "5") (pinfunction "5_5") (pintype "passive"))
      (node (ref "EXT_I2C_1") (pin "6") (pinfunction "6_6") (pintype "passive"))
      (node (ref "EXT_I2C_2") (pin "5") (pinfunction "5_5") (pintype "passive"))
      (node (ref "EXT_I2C_2") (pin "6") (pinfunction "6_6") (pintype "passive"))
      (node (ref "FRONTPANEL") (pin "10") (pinfunction "10_10") (pintype "passive"))
      (node (ref "FRONTPANEL") (pin "9") (pinfunction "9_9") (pintype "passive"))
      (node (ref "I2C_1") (pin "5") (pinfunction "5_5") (pintype "bidirectional"))
      (node (ref "I2C_1") (pin "6") (pinfunction "6_6") (pintype "bidirectional"))
      (node (ref "I2C_2") (pin "5") (pinfunction "5_5") (pintype "bidirectional"))
      (node (ref "I2C_2") (pin "6") (pinfunction "6_6") (pintype "bidirectional"))
      (node (ref "IC1") (pin "3") (pinfunction "GND_3") (pintype "power_in"))
      (node (ref "IC1") (pin "5") (pinfunction "EN_5") (pintype "input"))
      (node (ref "IC1") (pin "6") (pinfunction "GND_6") (pintype "power_in"))
      (node (ref "IC2") (pin "1") (pinfunction "GND_1") (pintype "power_in"))
      (node (ref "IC3") (pin "1") (pinfunction "GND_1") (pintype "power_in"))
      (node (ref "IC4") (pin "3") (pinfunction "A2_3") (pintype "input"))
      (node (ref "IC4") (pin "4") (pinfunction "A1_4") (pintype "input"))
      (node (ref "IC4") (pin "5") (pinfunction "A0_5") (pintype "input"))
      (node (ref "IC4") (pin "9") (pinfunction "GND_9") (pintype "power_in"))
      (node (ref "IC5") (pin "1") (pinfunction "GND_1") (pintype "power_in"))
      (node (ref "Q2") (pin "3") (pinfunction "S_3") (pintype "passive"))
      (node (ref "R3") (pin "P$1") (pinfunction "1_P$1") (pintype "passive"))
      (node (ref "R4") (pin "P$1") (pinfunction "1_P$1") (pintype "passive"))
      (node (ref "R7") (pin "P$1") (pinfunction "1_P$1") (pintype "passive"))
      (node (ref "ROM1") (pin "1") (pinfunction "A0_1") (pintype "input"))
      (node (ref "ROM1") (pin "2") (pinfunction "A1_2") (pintype "input"))
      (node (ref "ROM1") (pin "3") (pinfunction "A2_3") (pintype "input"))
      (node (ref "ROM1") (pin "4") (pinfunction "GND_4") (pintype "power_in"))
      (node (ref "ROM2") (pin "1") (pinfunction "A0_1") (pintype "input"))
      (node (ref "ROM2") (pin "2") (pinfunction "A1_2") (pintype "input"))
      (node (ref "ROM2") (pin "4") (pinfunction "GND_4") (pintype "power_in"))
      (node (ref "ROM3") (pin "1") (pinfunction "A0_1") (pintype "input"))
      (node (ref "ROM3") (pin "3") (pinfunction "A2_3") (pintype "input"))
      (node (ref "ROM3") (pin "4") (pinfunction "GND_4") (pintype "power_in"))
      (node (ref "ROM4") (pin "1") (pinfunction "A0_1") (pintype "input"))
      (node (ref "ROM4") (pin "4") (pinfunction "GND_4") (pintype "power_in"))
      (node (ref "SERIAL1") (pin "5") (pinfunction "5_5") (pintype "passive"))
      (node (ref "U1") (pin "1") (pinfunction "GND_1") (pintype "bidirectional"))
      (node (ref "U1") (pin "103") (pinfunction "GND_103") (pintype "bidirectional"))
      (node (ref "U1") (pin "104") (pinfunction "GND_104") (pintype "bidirectional"))
      (node (ref "U1") (pin "109") (pinfunction "GND_109") (pintype "bidirectional"))
      (node (ref "U1") (pin "110") (pinfunction "GND_110") (pintype "bidirectional"))
      (node (ref "U1") (pin "115") (pinfunction "GND_115") (pintype "bidirectional"))
      (node (ref "U1") (pin "116") (pinfunction "GND_116") (pintype "bidirectional"))
      (node (ref "U1") (pin "121") (pinfunction "GND_121") (pintype "bidirectional"))
      (node (ref "U1") (pin "122") (pinfunction "GND_122") (pintype "bidirectional"))
      (node (ref "U1") (pin "127") (pinfunction "GND_127") (pintype "bidirectional"))
      (node (ref "U1") (pin "13") (pinfunction "GND_13") (pintype "bidirectional"))
      (node (ref "U1") (pin "133") (pinfunction "GND_133") (pintype "bidirectional"))
      (node (ref "U1") (pin "134") (pinfunction "GND_134") (pintype "bidirectional"))
      (node (ref "U1") (pin "139") (pinfunction "GND_139") (pintype "bidirectional"))
      (node (ref "U1") (pin "140") (pinfunction "GND_140") (pintype "bidirectional"))
      (node (ref "U1") (pin "145") (pinfunction "GND_145") (pintype "bidirectional"))
      (node (ref "U1") (pin "146") (pinfunction "GND_146") (pintype "bidirectional"))
      (node (ref "U1") (pin "151") (pinfunction "GND_151") (pintype "bidirectional"))
      (node (ref "U1") (pin "152") (pinfunction "GND_152") (pintype "bidirectional"))
      (node (ref "U1") (pin "157") (pinfunction "GND_157") (pintype "bidirectional"))
      (node (ref "U1") (pin "163") (pinfunction "GND_163") (pintype "bidirectional"))
      (node (ref "U1") (pin "164") (pinfunction "GND_164") (pintype "bidirectional"))
      (node (ref "U1") (pin "169") (pinfunction "GND_169") (pintype "bidirectional"))
      (node (ref "U1") (pin "170") (pinfunction "GND_170") (pintype "bidirectional"))
      (node (ref "U1") (pin "181") (pinfunction "GND_181") (pintype "bidirectional"))
      (node (ref "U1") (pin "182") (pinfunction "GND_182") (pintype "bidirectional"))
      (node (ref "U1") (pin "187") (pinfunction "GND_187") (pintype "bidirectional"))
      (node (ref "U1") (pin "188") (pinfunction "GND_188") (pintype "bidirectional"))
      (node (ref "U1") (pin "19") (pinfunction "GND_19") (pintype "bidirectional"))
      (node (ref "U1") (pin "195") (pinfunction "GND_195") (pintype "bidirectional"))
      (node (ref "U1") (pin "196") (pinfunction "GND_196") (pintype "bidirectional"))
      (node (ref "U1") (pin "25") (pinfunction "GND_25") (pintype "bidirectional"))
      (node (ref "U1") (pin "26") (pinfunction "GND_26") (pintype "bidirectional"))
      (node (ref "U1") (pin "31") (pinfunction "GND_31") (pintype "bidirectional"))
      (node (ref "U1") (pin "32") (pinfunction "GND_32") (pintype "bidirectional"))
      (node (ref "U1") (pin "37") (pinfunction "GND_37") (pintype "bidirectional"))
      (node (ref "U1") (pin "38") (pinfunction "GND_38") (pintype "bidirectional"))
      (node (ref "U1") (pin "43") (pinfunction "GND_43") (pintype "bidirectional"))
      (node (ref "U1") (pin "44") (pinfunction "GND_44") (pintype "bidirectional"))
      (node (ref "U1") (pin "49") (pinfunction "GND_49") (pintype "bidirectional"))
      (node (ref "U1") (pin "50") (pinfunction "GND_50") (pintype "bidirectional"))
      (node (ref "U1") (pin "55") (pinfunction "GND_55") (pintype "bidirectional"))
      (node (ref "U1") (pin "56") (pinfunction "GND_56") (pintype "bidirectional"))
      (node (ref "U1") (pin "61") (pinfunction "GND_61") (pintype "bidirectional"))
      (node (ref "U1") (pin "62") (pinfunction "GND_62") (pintype "bidirectional"))
      (node (ref "U1") (pin "67") (pinfunction "GND_67") (pintype "bidirectional"))
      (node (ref "U1") (pin "68") (pinfunction "GND_68") (pintype "bidirectional"))
      (node (ref "U1") (pin "7") (pinfunction "GND_7") (pintype "bidirectional"))
      (node (ref "U1") (pin "73") (pinfunction "GND_73") (pintype "bidirectional"))
      (node (ref "U1") (pin "74") (pinfunction "GND_74") (pintype "bidirectional"))
      (node (ref "U1") (pin "79") (pinfunction "GND_79") (pintype "bidirectional"))
      (node (ref "U1") (pin "80") (pinfunction "GND_80") (pintype "bidirectional"))
      (node (ref "U1") (pin "85") (pinfunction "GND_85") (pintype "bidirectional"))
      (node (ref "U1") (pin "86") (pinfunction "GND_86") (pintype "bidirectional"))
      (node (ref "U1") (pin "91") (pinfunction "GND_91") (pintype "bidirectional"))
      (node (ref "U1") (pin "92") (pinfunction "GND_92") (pintype "bidirectional"))
      (node (ref "U1") (pin "97") (pinfunction "GND_97") (pintype "bidirectional"))
      (node (ref "U1") (pin "98") (pinfunction "GND_98") (pintype "bidirectional"))
      (node (ref "VIDEOCORE_JTAG") (pin "10") (pinfunction "10_10") (pintype "passive"))
      (node (ref "VIDEOCORE_JTAG") (pin "2") (pinfunction "2_2") (pintype "passive"))
      (node (ref "VIDEOCORE_JTAG") (pin "4") (pinfunction "4_4") (pintype "passive"))
      (node (ref "VIDEOCORE_JTAG") (pin "6") (pinfunction "6_6") (pintype "passive"))
      (node (ref "VIDEOCORE_JTAG") (pin "8") (pinfunction "8_8") (pintype "passive"))
    )
    (net (code "12") (name "GNDBREAK") (class "Default")
      (node (ref "CN1") (pin "GNDBREAK") (pinfunction "GNDBREAK_GNDBREAK") (pintype "power_in"))
    )
    (net (code "13") (name "GPIO4") (class "Default")
      (node (ref "EXP1") (pin "5") (pinfunction "5_5") (pintype "passive"))
      (node (ref "U1") (pin "15") (pinfunction "GPIO4_15") (pintype "bidirectional"))
    )
    (net (code "14") (name "GPIO5") (class "Default")
      (node (ref "EXP1") (pin "6") (pinfunction "6_6") (pintype "passive"))
      (node (ref "U1") (pin "17") (pinfunction "GPIO5_17") (pintype "bidirectional"))
    )
    (net (code "15") (name "GPIO6") (class "Default")
      (node (ref "EXP1") (pin "7") (pinfunction "7_7") (pintype "passive"))
      (node (ref "U1") (pin "21") (pinfunction "GPIO6_21") (pintype "bidirectional"))
    )
    (net (code "16") (name "GPIO7") (class "Default")
      (node (ref "EXP1") (pin "8") (pinfunction "8_8") (pintype "passive"))
      (node (ref "U1") (pin "23") (pinfunction "GPIO7_23") (pintype "bidirectional"))
    )
    (net (code "17") (name "GPIO8") (class "Default")
      (node (ref "EXP1") (pin "9") (pinfunction "9_9") (pintype "passive"))
      (node (ref "U1") (pin "27") (pinfunction "GPIO8_27") (pintype "bidirectional"))
    )
    (net (code "18") (name "GPIO9") (class "Default")
      (node (ref "EXP1") (pin "10") (pinfunction "10_10") (pintype "passive"))
      (node (ref "U1") (pin "29") (pinfunction "GPIO9_29") (pintype "bidirectional"))
    )
    (net (code "19") (name "GPIO10") (class "Default")
      (node (ref "EXP2") (pin "1") (pinfunction "1_1") (pintype "passive"))
      (node (ref "U1") (pin "33") (pinfunction "GPIO10_33") (pintype "bidirectional"))
    )
    (net (code "20") (name "GPIO11") (class "Default")
      (node (ref "EXP2") (pin "2") (pinfunction "2_2") (pintype "passive"))
      (node (ref "U1") (pin "35") (pinfunction "GPIO11_35") (pintype "bidirectional"))
    )
    (net (code "21") (name "GPIO12") (class "Default")
      (node (ref "EXP2") (pin "3") (pinfunction "3_3") (pintype "passive"))
      (node (ref "U1") (pin "45") (pinfunction "GPIO12_45") (pintype "bidirectional"))
    )
    (net (code "22") (name "GPIO13") (class "Default")
      (node (ref "EXP2") (pin "4") (pinfunction "4_4") (pintype "passive"))
      (node (ref "U1") (pin "47") (pinfunction "GPIO13_47") (pintype "bidirectional"))
    )
    (net (code "23") (name "GPIO17") (class "Default")
      (node (ref "EXP2") (pin "7") (pinfunction "7_7") (pintype "passive"))
      (node (ref "U1") (pin "59") (pinfunction "GPIO17_59") (pintype "bidirectional"))
    )
    (net (code "24") (name "GPIO18") (class "Default")
      (node (ref "EXP2") (pin "8") (pinfunction "8_8") (pintype "passive"))
      (node (ref "U1") (pin "63") (pinfunction "GPIO18_63") (pintype "bidirectional"))
    )
    (net (code "25") (name "GPIO19") (class "Default")
      (node (ref "EXP2") (pin "9") (pinfunction "9_9") (pintype "passive"))
      (node (ref "U1") (pin "65") (pinfunction "GPIO19_65") (pintype "bidirectional"))
    )
    (net (code "26") (name "GPIO20") (class "Default")
      (node (ref "EXP2") (pin "10") (pinfunction "10_10") (pintype "passive"))
      (node (ref "U1") (pin "69") (pinfunction "GPIO20_69") (pintype "bidirectional"))
    )
    (net (code "27") (name "GPIO21") (class "Default")
      (node (ref "EXP3") (pin "1") (pinfunction "1_1") (pintype "passive"))
      (node (ref "U1") (pin "71") (pinfunction "GPIO21_71") (pintype "bidirectional"))
    )
    (net (code "28") (name "GPIO22") (class "Default")
      (node (ref "EXP3") (pin "2") (pinfunction "2_2") (pintype "passive"))
      (node (ref "U1") (pin "75") (pinfunction "GPIO22_75") (pintype "bidirectional"))
    )
    (net (code "29") (name "GPIO23") (class "Default")
      (node (ref "EXP3") (pin "3") (pinfunction "3_3") (pintype "passive"))
      (node (ref "U1") (pin "77") (pinfunction "GPIO23_77") (pintype "bidirectional"))
    )
    (net (code "30") (name "GPIO24") (class "Default")
      (node (ref "EXP3") (pin "4") (pinfunction "4_4") (pintype "passive"))
      (node (ref "U1") (pin "81") (pinfunction "GPIO24_81") (pintype "bidirectional"))
    )
    (net (code "31") (name "GPIO25") (class "Default")
      (node (ref "EXP3") (pin "5") (pinfunction "5_5") (pintype "passive"))
      (node (ref "U1") (pin "83") (pinfunction "GPIO25_83") (pintype "bidirectional"))
    )
    (net (code "32") (name "GPIO26") (class "Default")
      (node (ref "EXP3") (pin "6") (pinfunction "6_6") (pintype "passive"))
      (node (ref "U1") (pin "87") (pinfunction "GPIO26_87") (pintype "bidirectional"))
    )
    (net (code "33") (name "GPIO27") (class "Default")
      (node (ref "EXP3") (pin "7") (pinfunction "7_7") (pintype "passive"))
      (node (ref "U1") (pin "89") (pinfunction "GPIO27_89") (pintype "bidirectional"))
    )
    (net (code "34") (name "GPIO28") (class "Default")
      (node (ref "EXP3") (pin "8") (pinfunction "8_8") (pintype "passive"))
      (node (ref "U1") (pin "28") (pinfunction "GPIO28_28") (pintype "bidirectional"))
    )
    (net (code "35") (name "GPIO29") (class "Default")
      (node (ref "EXP3") (pin "9") (pinfunction "9_9") (pintype "passive"))
      (node (ref "U1") (pin "30") (pinfunction "GPIO29_30") (pintype "bidirectional"))
    )
    (net (code "36") (name "GPIO30") (class "Default")
      (node (ref "EXP3") (pin "10") (pinfunction "10_10") (pintype "passive"))
      (node (ref "U1") (pin "34") (pinfunction "GPIO30_34") (pintype "bidirectional"))
    )
    (net (code "37") (name "GPIO31") (class "Default")
      (node (ref "EXP4") (pin "1") (pinfunction "1_1") (pintype "passive"))
      (node (ref "U1") (pin "36") (pinfunction "GPIO31_36") (pintype "bidirectional"))
    )
    (net (code "38") (name "GPIO32") (class "Default")
      (node (ref "EXP4") (pin "2") (pinfunction "2_2") (pintype "passive"))
      (node (ref "U1") (pin "46") (pinfunction "GPIO32_46") (pintype "bidirectional"))
    )
    (net (code "39") (name "GPIO33") (class "Default")
      (node (ref "EXP4") (pin "3") (pinfunction "3_3") (pintype "passive"))
      (node (ref "U1") (pin "48") (pinfunction "GPIO33_48") (pintype "bidirectional"))
    )
    (net (code "40") (name "GPIO34") (class "Default")
      (node (ref "EXP4") (pin "4") (pinfunction "4_4") (pintype "passive"))
      (node (ref "U1") (pin "52") (pinfunction "GPIO34_52") (pintype "bidirectional"))
    )
    (net (code "41") (name "GPIO35") (class "Default")
      (node (ref "EXP4") (pin "5") (pinfunction "5_5") (pintype "passive"))
      (node (ref "U1") (pin "54") (pinfunction "GPIO35_54") (pintype "bidirectional"))
    )
    (net (code "42") (name "GPIO36") (class "Default")
      (node (ref "EXP4") (pin "6") (pinfunction "6_6") (pintype "passive"))
      (node (ref "U1") (pin "58") (pinfunction "GPIO36_58") (pintype "bidirectional"))
    )
    (net (code "43") (name "GPIO37") (class "Default")
      (node (ref "EXP4") (pin "7") (pinfunction "7_7") (pintype "passive"))
      (node (ref "U1") (pin "60") (pinfunction "GPIO37_60") (pintype "bidirectional"))
    )
    (net (code "44") (name "GPIO38") (class "Default")
      (node (ref "EXP4") (pin "8") (pinfunction "8_8") (pintype "passive"))
      (node (ref "U1") (pin "64") (pinfunction "GPIO38_64") (pintype "bidirectional"))
    )
    (net (code "45") (name "GPIO39") (class "Default")
      (node (ref "EXP4") (pin "9") (pinfunction "9_9") (pintype "passive"))
      (node (ref "U1") (pin "66") (pinfunction "GPIO39_66") (pintype "bidirectional"))
    )
    (net (code "46") (name "GPIO40") (class "Default")
      (node (ref "EXP4") (pin "10") (pinfunction "10_10") (pintype "passive"))
      (node (ref "R5") (pin "P$1") (pinfunction "1_P$1") (pintype "passive"))
      (node (ref "U1") (pin "70") (pinfunction "GPIO40_70") (pintype "bidirectional"))
    )
    (net (code "47") (name "GPIO41") (class "Default")
      (node (ref "EXP5") (pin "1") (pinfunction "1_1") (pintype "passive"))
      (node (ref "R6") (pin "P$1") (pinfunction "1_P$1") (pintype "passive"))
      (node (ref "U1") (pin "72") (pinfunction "GPIO41_72") (pintype "bidirectional"))
    )
    (net (code "48") (name "GPIO42") (class "Default")
      (node (ref "EXP5") (pin "2") (pinfunction "2_2") (pintype "passive"))
      (node (ref "U1") (pin "76") (pinfunction "GPIO42_76") (pintype "bidirectional"))
    )
    (net (code "49") (name "GPIO43") (class "Default")
      (node (ref "EXP5") (pin "3") (pinfunction "3_3") (pintype "passive"))
      (node (ref "U1") (pin "78") (pinfunction "GPIO43_78") (pintype "bidirectional"))
    )
    (net (code "50") (name "GPIO44") (class "Default")
      (node (ref "EXP5") (pin "4") (pinfunction "4_4") (pintype "passive"))
      (node (ref "U1") (pin "82") (pinfunction "GPIO44_82") (pintype "bidirectional"))
    )
    (net (code "51") (name "GPIO45") (class "Default")
      (node (ref "EXP5") (pin "5") (pinfunction "5_5") (pintype "passive"))
      (node (ref "U1") (pin "84") (pinfunction "GPIO45_84") (pintype "bidirectional"))
    )
    (net (code "52") (name "HDMI_CEC") (class "Default")
      (node (ref "CHEATER") (pin "15") (pinfunction "15_15") (pintype "passive"))
      (node (ref "U1") (pin "171") (pinfunction "HDMI_CEC_171") (pintype "bidirectional"))
    )
    (net (code "53") (name "HDMI_CK_N") (class "Default")
      (node (ref "CHEATER") (pin "2") (pinfunction "2_2") (pintype "passive"))
      (node (ref "U1") (pin "111") (pinfunction "HDMI_CK_N_111") (pintype "bidirectional"))
    )
    (net (code "54") (name "HDMI_CK_P") (class "Default")
      (node (ref "CHEATER") (pin "4") (pinfunction "4_4") (pintype "passive"))
      (node (ref "U1") (pin "113") (pinfunction "HDMI_CK_P_113") (pintype "bidirectional"))
    )
    (net (code "55") (name "HDMI_D0_N") (class "Default")
      (node (ref "CHEATER") (pin "6") (pinfunction "6_6") (pintype "passive"))
      (node (ref "U1") (pin "117") (pinfunction "HDMI_D0_N_117") (pintype "bidirectional"))
    )
    (net (code "56") (name "HDMI_D0_P") (class "Default")
      (node (ref "CHEATER") (pin "8") (pinfunction "8_8") (pintype "passive"))
      (node (ref "U1") (pin "119") (pinfunction "HDMI_D0_P_119") (pintype "bidirectional"))
    )
    (net (code "57") (name "HDMI_D1_N") (class "Default")
      (node (ref "CHEATER") (pin "10") (pinfunction "10_10") (pintype "passive"))
      (node (ref "U1") (pin "123") (pinfunction "HDMI_D1_N_123") (pintype "bidirectional"))
    )
    (net (code "58") (name "HDMI_D1_P") (class "Default")
      (node (ref "CHEATER") (pin "12") (pinfunction "12_12") (pintype "passive"))
      (node (ref "U1") (pin "125") (pinfunction "HDMI_D1_P_125") (pintype "bidirectional"))
    )
    (net (code "59") (name "HDMI_D2_N") (class "Default")
      (node (ref "CHEATER") (pin "14") (pinfunction "14_14") (pintype "passive"))
      (node (ref "U1") (pin "129") (pinfunction "HDMI_D2_N_129") (pintype "bidirectional"))
    )
    (net (code "60") (name "HDMI_D2_P") (class "Default")
      (node (ref "CHEATER") (pin "16") (pinfunction "16_16") (pintype "passive"))
      (node (ref "U1") (pin "131") (pinfunction "HDMI_D2_P_131") (pintype "bidirectional"))
    )
    (net (code "61") (name "HDMI_SCL") (class "Default")
      (node (ref "CHEATER") (pin "7") (pinfunction "7_7") (pintype "passive"))
      (node (ref "U1") (pin "175") (pinfunction "HDMI_SCL_175") (pintype "bidirectional"))
    )
    (net (code "62") (name "HDMI_SDA") (class "Default")
      (node (ref "CHEATER") (pin "11") (pinfunction "11_11") (pintype "passive"))
      (node (ref "U1") (pin "173") (pinfunction "HDMI_SDA_173") (pintype "bidirectional"))
    )
    (net (code "63") (name "IO_RST") (class "Default")
      (node (ref "IC4") (pin "6") (pinfunction "/RST_6") (pintype "input"))
      (node (ref "R9") (pin "P$2") (pinfunction "2_P$2") (pintype "passive"))
    )
    (net (code "64") (name "LED_ACTIVITY") (class "Default")
      (node (ref "FRONTPANEL") (pin "6") (pinfunction "6_6") (pintype "passive"))
    )
    (net (code "65") (name "LED_NOTIFICATION") (class "Default")
      (node (ref "FRONTPANEL") (pin "8") (pinfunction "8_8") (pintype "passive"))
      (node (ref "IC4") (pin "16") (pinfunction "GP6_16") (pintype "bidirectional"))
      (node (ref "R7") (pin "P$8") (pinfunction "8_P$8") (pintype "passive"))
    )
    (net (code "66") (name "LED_ON") (class "Default")
      (node (ref "FRONTPANEL") (pin "4") (pinfunction "4_4") (pintype "passive"))
    )
    (net (code "67") (name "LOUT_L") (class "Default")
      (node (ref "AUDIO") (pin "TIP") (pinfunction "LEFT_TIP") (pintype "bidirectional"))
      (node (ref "C12") (pin "1") (pinfunction "1_1") (pintype "passive"))
      (node (ref "C7") (pin "2") (pinfunction "2_2") (pintype "passive"))
      (node (ref "U$1") (pin "2") (pinfunction "INPUT_2") (pintype "input"))
    )
    (net (code "68") (name "LOUT_R") (class "Default")
      (node (ref "AUDIO") (pin "RING") (pinfunction "RIGHT_RING") (pintype "bidirectional"))
      (node (ref "C15") (pin "1") (pinfunction "1_1") (pintype "passive"))
      (node (ref "C6") (pin "2") (pinfunction "2_2") (pintype "passive"))
      (node (ref "U$2") (pin "2") (pinfunction "INPUT_2") (pintype "input"))
    )
    (net (code "69") (name "N$6") (class "Default")
      (node (ref "U1") (pin "90") (pinfunction "GPIO47_1V8_90") (pintype "bidirectional"))
    )
    (net (code "70") (name "N$7") (class "Default")
      (node (ref "U1") (pin "2") (pinfunction "EMMC_DISABLE_N_2") (pintype "bidirectional"))
    )
    (net (code "71") (name "N$9") (class "Default")
      (node (ref "U1") (pin "168") (pinfunction "USB_OTGID_168") (pintype "bidirectional"))
    )
    (net (code "72") (name "N$14") (class "Default")
      (node (ref "IC4") (pin "8") (pinfunction "INT_8") (pintype "output"))
    )
    (net (code "73") (name "N$16") (class "Default")
      (node (ref "IC4") (pin "15") (pinfunction "GP5_15") (pintype "bidirectional"))
      (node (ref "R7") (pin "P$7") (pinfunction "7_P$7") (pintype "passive"))
    )
    (net (code "74") (name "N$17") (class "Default")
      (node (ref "IC4") (pin "14") (pinfunction "GP4_14") (pintype "bidirectional"))
      (node (ref "R7") (pin "P$6") (pinfunction "6_P$6") (pintype "passive"))
    )
    (net (code "75") (name "N$18") (class "Default")
      (node (ref "IC4") (pin "13") (pinfunction "GP3_13") (pintype "bidirectional"))
      (node (ref "R7") (pin "P$5") (pinfunction "5_P$5") (pintype "passive"))
    )
    (net (code "76") (name "N$19") (class "Default")
      (node (ref "IC4") (pin "12") (pinfunction "GP2_12") (pintype "bidirectional"))
      (node (ref "R7") (pin "P$4") (pinfunction "4_P$4") (pintype "passive"))
    )
    (net (code "77") (name "N$20") (class "Default")
      (node (ref "IC4") (pin "11") (pinfunction "GP1_11") (pintype "bidirectional"))
      (node (ref "R7") (pin "P$3") (pinfunction "3_P$3") (pintype "passive"))
    )
    (net (code "78") (name "N$21") (class "Default")
      (node (ref "IC4") (pin "10") (pinfunction "GP0_10") (pintype "bidirectional"))
      (node (ref "R7") (pin "P$2") (pinfunction "2_P$2") (pintype "passive"))
    )
    (net (code "79") (name "N$25") (class "Default")
      (node (ref "U1") (pin "88") (pinfunction "GPIO46_1V8_88") (pintype "bidirectional"))
    )
    (net (code "80") (name "NC") (class "Default")
      (node (ref "EXP5") (pin "6") (pinfunction "6_6") (pintype "passive"))
    )
    (net (code "81") (name "Net-(CN1-PadPWR)") (class "Default")
      (node (ref "CN1") (pin "PWR") (pinfunction "PWR_PWR") (pintype "power_in"))
      (node (ref "PWR_SWITCH") (pin "1") (pinfunction "1_1") (pintype "passive"))
    )
    (net (code "82") (name "Net-(IC1-OUT)") (class "Default")
      (node (ref "D1") (pin "C") (pinfunction "C_C") (pintype "passive"))
      (node (ref "IC1") (pin "2") (pinfunction "OUT_2") (pintype "output"))
      (node (ref "L1") (pin "1") (pinfunction "1_1") (pintype "passive"))
    )
    (net (code "83") (name "Net-(Q2-G)") (class "Default")
      (node (ref "Q2") (pin "2") (pinfunction "G_2") (pintype "passive"))
      (node (ref "R8") (pin "P$2") (pinfunction "2_P$2") (pintype "passive"))
    )
    (net (code "84") (name "Net-(U$1-OUT1)") (class "Default")
      (node (ref "SPKR_L") (pin "2") (pinfunction "2_2") (pintype "passive"))
      (node (ref "U$1") (pin "5") (pinfunction "OUT1_5") (pintype "output"))
    )
    (net (code "85") (name "Net-(U$1-OUT2)") (class "Default")
      (node (ref "SPKR_L") (pin "1") (pinfunction "1_1") (pintype "passive"))
      (node (ref "U$1") (pin "8") (pinfunction "OUT2_8") (pintype "output"))
    )
    (net (code "86") (name "Net-(U$2-OUT1)") (class "Default")
      (node (ref "SPKR_R") (pin "2") (pinfunction "2_2") (pintype "passive"))
      (node (ref "U$2") (pin "5") (pinfunction "OUT1_5") (pintype "output"))
    )
    (net (code "87") (name "Net-(U$2-OUT2)") (class "Default")
      (node (ref "SPKR_R") (pin "1") (pinfunction "1_1") (pintype "passive"))
      (node (ref "U$2") (pin "8") (pinfunction "OUT2_8") (pintype "output"))
    )
    (net (code "88") (name "Net-(U1F-VC_TCK)") (class "Default")
      (node (ref "U1") (pin "180") (pinfunction "VC_TCK_180") (pintype "bidirectional"))
      (node (ref "VIDEOCORE_JTAG") (pin "9") (pinfunction "9_9") (pintype "passive"))
    )
    (net (code "89") (name "Net-(U1F-VC_TDI)") (class "Default")
      (node (ref "U1") (pin "174") (pinfunction "VC_TDI_174") (pintype "bidirectional"))
      (node (ref "VIDEOCORE_JTAG") (pin "3") (pinfunction "3_3") (pintype "passive"))
    )
    (net (code "90") (name "Net-(U1F-VC_TDO)") (class "Default")
      (node (ref "U1") (pin "178") (pinfunction "VC_TDO_178") (pintype "bidirectional"))
      (node (ref "VIDEOCORE_JTAG") (pin "7") (pinfunction "7_7") (pintype "passive"))
    )
    (net (code "91") (name "Net-(U1F-VC_TMS)") (class "Default")
      (node (ref "U1") (pin "176") (pinfunction "VC_TMS_176") (pintype "bidirectional"))
      (node (ref "VIDEOCORE_JTAG") (pin "5") (pinfunction "5_5") (pintype "passive"))
    )
    (net (code "92") (name "Net-(U1F-VC_TSRT_N)") (class "Default")
      (node (ref "U1") (pin "172") (pinfunction "VC_TSRT_N_172") (pintype "bidirectional"))
      (node (ref "VIDEOCORE_JTAG") (pin "1") (pinfunction "1_1") (pintype "passive"))
    )
    (net (code "93") (name "PORT_RX") (class "Default")
      (node (ref "SERIAL1") (pin "2") (pinfunction "2_2") (pintype "passive"))
      (node (ref "SERIAL1_PORTFLIP") (pin "3") (pinfunction "3_3") (pintype "bidirectional"))
    )
    (net (code "94") (name "PORT_TX") (class "Default")
      (node (ref "SERIAL1") (pin "3") (pinfunction "3_3") (pintype "passive"))
      (node (ref "SERIAL1_PORTFLIP") (pin "4") (pinfunction "4_4") (pintype "bidirectional"))
    )
    (net (code "95") (name "PWM0_R") (class "Default")
      (node (ref "C6") (pin "1") (pinfunction "1_1") (pintype "passive"))
      (node (ref "C8") (pin "1") (pinfunction "1_1") (pintype "passive"))
      (node (ref "R3") (pin "P$2") (pinfunction "2_P$2") (pintype "passive"))
      (node (ref "R5") (pin "P$2") (pinfunction "2_P$2") (pintype "passive"))
    )
    (net (code "96") (name "PWM1_L") (class "Default")
      (node (ref "C7") (pin "1") (pinfunction "1_1") (pintype "passive"))
      (node (ref "C9") (pin "1") (pinfunction "1_1") (pintype "passive"))
      (node (ref "R4") (pin "P$2") (pinfunction "2_P$2") (pintype "passive"))
      (node (ref "R6") (pin "P$2") (pinfunction "2_P$2") (pintype "passive"))
    )
    (net (code "97") (name "RI") (class "Default")
      (node (ref "SERIAL1") (pin "9") (pinfunction "9_9") (pintype "passive"))
    )
    (net (code "98") (name "RTS") (class "Default")
      (node (ref "SERIAL1") (pin "7") (pinfunction "7_7") (pintype "passive"))
    )
    (net (code "99") (name "RUN") (class "Default")
      (node (ref "U1") (pin "177") (pinfunction "RUN_177") (pintype "bidirectional"))
    )
    (net (code "100") (name "RXD0") (class "Default")
      (node (ref "EXP2") (pin "6") (pinfunction "6_6") (pintype "passive"))
      (node (ref "SERIAL1_PORTFLIP") (pin "1") (pinfunction "1_1") (pintype "bidirectional"))
      (node (ref "SERIAL1_PORTFLIP") (pin "6") (pinfunction "6_6") (pintype "bidirectional"))
      (node (ref "U1") (pin "53") (pinfunction "GPIO15_53") (pintype "bidirectional"))
    )
    (net (code "101") (name "SCL") (class "Default")
      (node (ref "EXP1") (pin "2") (pinfunction "2_2") (pintype "passive"))
      (node (ref "EXT_I2C_1") (pin "3") (pinfunction "3_3") (pintype "passive"))
      (node (ref "EXT_I2C_2") (pin "3") (pinfunction "3_3") (pintype "passive"))
      (node (ref "FRONTPANEL") (pin "3") (pinfunction "3_3") (pintype "passive"))
      (node (ref "I2C_1") (pin "3") (pinfunction "3_3") (pintype "bidirectional"))
      (node (ref "I2C_2") (pin "3") (pinfunction "3_3") (pintype "bidirectional"))
      (node (ref "IC4") (pin "1") (pinfunction "SCL_1") (pintype "bidirectional"))
      (node (ref "R1") (pin "P$1") (pinfunction "1_P$1") (pintype "passive"))
      (node (ref "ROM1") (pin "6") (pinfunction "SCL_6") (pintype "input"))
      (node (ref "ROM2") (pin "6") (pinfunction "SCL_6") (pintype "input"))
      (node (ref "ROM3") (pin "6") (pinfunction "SCL_6") (pintype "input"))
      (node (ref "ROM4") (pin "6") (pinfunction "SCL_6") (pintype "input"))
      (node (ref "U1") (pin "5") (pinfunction "GPIO1_5") (pintype "bidirectional"))
    )
    (net (code "102") (name "SCL1") (class "Default")
      (node (ref "EXP1") (pin "4") (pinfunction "4_4") (pintype "passive"))
      (node (ref "U1") (pin "11") (pinfunction "GPIO3_11") (pintype "bidirectional"))
    )
    (net (code "103") (name "SDA") (class "Default")
      (node (ref "EXP1") (pin "1") (pinfunction "1_1") (pintype "passive"))
      (node (ref "EXT_I2C_1") (pin "4") (pinfunction "4_4") (pintype "passive"))
      (node (ref "EXT_I2C_2") (pin "4") (pinfunction "4_4") (pintype "passive"))
      (node (ref "FRONTPANEL") (pin "5") (pinfunction "5_5") (pintype "passive"))
      (node (ref "I2C_1") (pin "4") (pinfunction "4_4") (pintype "bidirectional"))
      (node (ref "I2C_2") (pin "4") (pinfunction "4_4") (pintype "bidirectional"))
      (node (ref "IC4") (pin "2") (pinfunction "SDA_2") (pintype "bidirectional"))
      (node (ref "R2") (pin "P$1") (pinfunction "1_P$1") (pintype "passive"))
      (node (ref "ROM1") (pin "5") (pinfunction "SDA_5") (pintype "bidirectional"))
      (node (ref "ROM2") (pin "5") (pinfunction "SDA_5") (pintype "bidirectional"))
      (node (ref "ROM3") (pin "5") (pinfunction "SDA_5") (pintype "bidirectional"))
      (node (ref "ROM4") (pin "5") (pinfunction "SDA_5") (pintype "bidirectional"))
      (node (ref "U1") (pin "3") (pinfunction "GPIO0_3") (pintype "bidirectional"))
    )
    (net (code "104") (name "SDA1") (class "Default")
      (node (ref "EXP1") (pin "3") (pinfunction "3_3") (pintype "passive"))
      (node (ref "U1") (pin "9") (pinfunction "GPIO2_9") (pintype "bidirectional"))
    )
    (net (code "105") (name "SPKR_ENABLE") (class "Default")
      (node (ref "IC4") (pin "17") (pinfunction "GP7_17") (pintype "bidirectional"))
      (node (ref "R7") (pin "P$9") (pinfunction "9_P$9") (pintype "passive"))
      (node (ref "R8") (pin "P$1") (pinfunction "1_P$1") (pintype "passive"))
    )
    (net (code "106") (name "STATUS_LED_N") (class "Default")
      (node (ref "U1") (pin "57") (pinfunction "GPIO16_57") (pintype "bidirectional"))
    )
    (net (code "107") (name "SW_PWR_ON") (class "Default")
      (node (ref "FRONTPANEL") (pin "2") (pinfunction "2_2") (pintype "passive"))
    )
    (net (code "108") (name "TXD0") (class "Default")
      (node (ref "EXP2") (pin "5") (pinfunction "5_5") (pintype "passive"))
      (node (ref "SERIAL1_PORTFLIP") (pin "2") (pinfunction "2_2") (pintype "bidirectional"))
      (node (ref "SERIAL1_PORTFLIP") (pin "5") (pinfunction "5_5") (pintype "bidirectional"))
      (node (ref "U1") (pin "51") (pinfunction "GPIO14_51") (pintype "bidirectional"))
    )
    (net (code "109") (name "USB+") (class "Default")
      (node (ref "EXP5") (pin "10") (pinfunction "10_10") (pintype "passive"))
      (node (ref "USB_POLARITY") (pin "1") (pinfunction "1_1") (pintype "bidirectional"))
      (node (ref "USB_POLARITY") (pin "6") (pinfunction "6_6") (pintype "bidirectional"))
    )
    (net (code "110") (name "USB-") (class "Default")
      (node (ref "EXP5") (pin "9") (pinfunction "9_9") (pintype "passive"))
      (node (ref "USB_POLARITY") (pin "2") (pinfunction "2_2") (pintype "bidirectional"))
      (node (ref "USB_POLARITY") (pin "5") (pinfunction "5_5") (pintype "bidirectional"))
    )
    (net (code "111") (name "USB_D+") (class "Default")
      (node (ref "U1") (pin "165") (pinfunction "USB_DP_P_165") (pintype "bidirectional"))
      (node (ref "USB_POLARITY") (pin "3") (pinfunction "3_3") (pintype "bidirectional"))
    )
    (net (code "112") (name "USB_D-") (class "Default")
      (node (ref "U1") (pin "167") (pinfunction "USB_DM_N_167") (pintype "bidirectional"))
      (node (ref "USB_POLARITY") (pin "4") (pinfunction "4_4") (pintype "bidirectional"))
    )
    (net (code "113") (name "V+") (class "Default")
      (node (ref "EXP6") (pin "10") (pinfunction "10_10") (pintype "passive"))
      (node (ref "EXP6") (pin "9") (pinfunction "9_9") (pintype "passive"))
      (node (ref "IC1") (pin "1") (pinfunction "IN_1") (pintype "input"))
      (node (ref "PWR_SWITCH") (pin "2") (pinfunction "2_2") (pintype "passive"))
    )
    (net (code "114") (name "unconnected-(ROM1-WP-Pad7)") (class "Default")
      (node (ref "ROM1") (pin "7") (pinfunction "WP_7") (pintype "input"))
    )
    (net (code "115") (name "unconnected-(ROM2-WP-Pad7)") (class "Default")
      (node (ref "ROM2") (pin "7") (pinfunction "WP_7") (pintype "input"))
    )
    (net (code "116") (name "unconnected-(ROM3-WP-Pad7)") (class "Default")
      (node (ref "ROM3") (pin "7") (pinfunction "WP_7") (pintype "input"))
    )
    (net (code "117") (name "unconnected-(ROM4-WP-Pad7)") (class "Default")
      (node (ref "ROM4") (pin "7") (pinfunction "WP_7") (pintype "input"))
    )
    (net (code "118") (name "unconnected-(U1A-CAM0_C_N-Pad144)") (class "Default")
      (node (ref "U1") (pin "144") (pinfunction "CAM0_C_N_144") (pintype "bidirectional"))
    )
    (net (code "119") (name "unconnected-(U1A-CAM0_C_P-Pad142)") (class "Default")
      (node (ref "U1") (pin "142") (pinfunction "CAM0_C_P_142") (pintype "bidirectional"))
    )
    (net (code "120") (name "unconnected-(U1A-CAM0_D0_N-Pad138)") (class "Default")
      (node (ref "U1") (pin "138") (pinfunction "CAM0_D0_N_138") (pintype "bidirectional"))
    )
    (net (code "121") (name "unconnected-(U1A-CAM0_D0_P-Pad136)") (class "Default")
      (node (ref "U1") (pin "136") (pinfunction "CAM0_D0_P_136") (pintype "bidirectional"))
    )
    (net (code "122") (name "unconnected-(U1A-CAM0_D1_N-Pad150)") (class "Default")
      (node (ref "U1") (pin "150") (pinfunction "CAM0_D1_N_150") (pintype "bidirectional"))
    )
    (net (code "123") (name "unconnected-(U1A-CAM0_D1_P-Pad148)") (class "Default")
      (node (ref "U1") (pin "148") (pinfunction "CAM0_D1_P_148") (pintype "bidirectional"))
    )
    (net (code "124") (name "unconnected-(U1A-CAM1_C_N-Pad149)") (class "Default")
      (node (ref "U1") (pin "149") (pinfunction "CAM1_C_N_149") (pintype "bidirectional"))
    )
    (net (code "125") (name "unconnected-(U1A-CAM1_C_P-Pad147)") (class "Default")
      (node (ref "U1") (pin "147") (pinfunction "CAM1_C_P_147") (pintype "bidirectional"))
    )
    (net (code "126") (name "unconnected-(U1A-CAM1_D0_N-Pad161)") (class "Default")
      (node (ref "U1") (pin "161") (pinfunction "CAM1_D0_N_161") (pintype "bidirectional"))
    )
    (net (code "127") (name "unconnected-(U1A-CAM1_D0_P-Pad159)") (class "Default")
      (node (ref "U1") (pin "159") (pinfunction "CAM1_D0_P_159") (pintype "bidirectional"))
    )
    (net (code "128") (name "unconnected-(U1A-CAM1_D1_N-Pad155)") (class "Default")
      (node (ref "U1") (pin "155") (pinfunction "CAM1_D1_N_155") (pintype "bidirectional"))
    )
    (net (code "129") (name "unconnected-(U1A-CAM1_D1_P-Pad153)") (class "Default")
      (node (ref "U1") (pin "153") (pinfunction "CAM1_D1_P_153") (pintype "bidirectional"))
    )
    (net (code "130") (name "unconnected-(U1A-CAM1_D2_N-Pad143)") (class "Default")
      (node (ref "U1") (pin "143") (pinfunction "CAM1_D2_N_143") (pintype "bidirectional"))
    )
    (net (code "131") (name "unconnected-(U1A-CAM1_D2_P-Pad141)") (class "Default")
      (node (ref "U1") (pin "141") (pinfunction "CAM1_D2_P_141") (pintype "bidirectional"))
    )
    (net (code "132") (name "unconnected-(U1A-CAM1_D3_N-Pad137)") (class "Default")
      (node (ref "U1") (pin "137") (pinfunction "CAM1_D3_N_137") (pintype "bidirectional"))
    )
    (net (code "133") (name "unconnected-(U1A-CAM1_D3_P-Pad135)") (class "Default")
      (node (ref "U1") (pin "135") (pinfunction "CAM1_D3_P_135") (pintype "bidirectional"))
    )
    (net (code "134") (name "unconnected-(U1B-DSI0_C_N-Pad105)") (class "Default")
      (node (ref "U1") (pin "105") (pinfunction "DSI0_C_N_105") (pintype "bidirectional"))
    )
    (net (code "135") (name "unconnected-(U1B-DSI0_C_P-Pad107)") (class "Default")
      (node (ref "U1") (pin "107") (pinfunction "DSI0_C_P_107") (pintype "bidirectional"))
    )
    (net (code "136") (name "unconnected-(U1B-DSI0_D0_N-Pad99)") (class "Default")
      (node (ref "U1") (pin "99") (pinfunction "DSI0_D0_N_99") (pintype "bidirectional"))
    )
    (net (code "137") (name "unconnected-(U1B-DSI0_D0_P-Pad101)") (class "Default")
      (node (ref "U1") (pin "101") (pinfunction "DSI0_D0_P_101") (pintype "bidirectional"))
    )
    (net (code "138") (name "unconnected-(U1B-DSI0_D1_N-Pad93)") (class "Default")
      (node (ref "U1") (pin "93") (pinfunction "DSI0_D1_N_93") (pintype "bidirectional"))
    )
    (net (code "139") (name "unconnected-(U1B-DSI0_D1_P-Pad95)") (class "Default")
      (node (ref "U1") (pin "95") (pinfunction "DSI0_D1_P_95") (pintype "bidirectional"))
    )
    (net (code "140") (name "unconnected-(U1B-DSI1_C_N-Pad102)") (class "Default")
      (node (ref "U1") (pin "102") (pinfunction "DSI1_C_N_102") (pintype "bidirectional"))
    )
    (net (code "141") (name "unconnected-(U1B-DSI1_C_P-Pad100)") (class "Default")
      (node (ref "U1") (pin "100") (pinfunction "DSI1_C_P_100") (pintype "bidirectional"))
    )
    (net (code "142") (name "unconnected-(U1B-DSI1_D0_N-Pad96)") (class "Default")
      (node (ref "U1") (pin "96") (pinfunction "DSI1_D0_N_96") (pintype "bidirectional"))
    )
    (net (code "143") (name "unconnected-(U1B-DSI1_D0_P-Pad94)") (class "Default")
      (node (ref "U1") (pin "94") (pinfunction "DSI1_D0_P_94") (pintype "bidirectional"))
    )
    (net (code "144") (name "unconnected-(U1B-DSI1_D1_N-Pad120)") (class "Default")
      (node (ref "U1") (pin "120") (pinfunction "DSI1_D1_N_120") (pintype "bidirectional"))
    )
    (net (code "145") (name "unconnected-(U1B-DSI1_D1_P-Pad118)") (class "Default")
      (node (ref "U1") (pin "118") (pinfunction "DSI1_D1_P_118") (pintype "bidirectional"))
    )
    (net (code "146") (name "unconnected-(U1B-DSI1_D2_N-Pad114)") (class "Default")
      (node (ref "U1") (pin "114") (pinfunction "DSI1_D2_N_114") (pintype "bidirectional"))
    )
    (net (code "147") (name "unconnected-(U1B-DSI1_D2_P-Pad112)") (class "Default")
      (node (ref "U1") (pin "112") (pinfunction "DSI1_D2_P_112") (pintype "bidirectional"))
    )
    (net (code "148") (name "unconnected-(U1B-DSI1_D3_N-Pad108)") (class "Default")
      (node (ref "U1") (pin "108") (pinfunction "DSI1_D3_N_108") (pintype "bidirectional"))
    )
    (net (code "149") (name "unconnected-(U1B-DSI1_D3_P-Pad106)") (class "Default")
      (node (ref "U1") (pin "106") (pinfunction "DSI1_D3_P_106") (pintype "bidirectional"))
    )
    (net (code "150") (name "unconnected-(U1G-VDD_CORE-Pad179)") (class "Default")
      (node (ref "U1") (pin "179") (pinfunction "VDD_CORE_179") (pintype "bidirectional"))
    )
    (net (code "151") (name "unconnected-(U1I-TVDAC-Pad166)") (class "Default")
      (node (ref "U1") (pin "166") (pinfunction "TVDAC_166") (pintype "bidirectional"))
    )
  )
)
